# DigitalBackend_v1.net
KiCad netlist of a schematic drawn in EAGLE
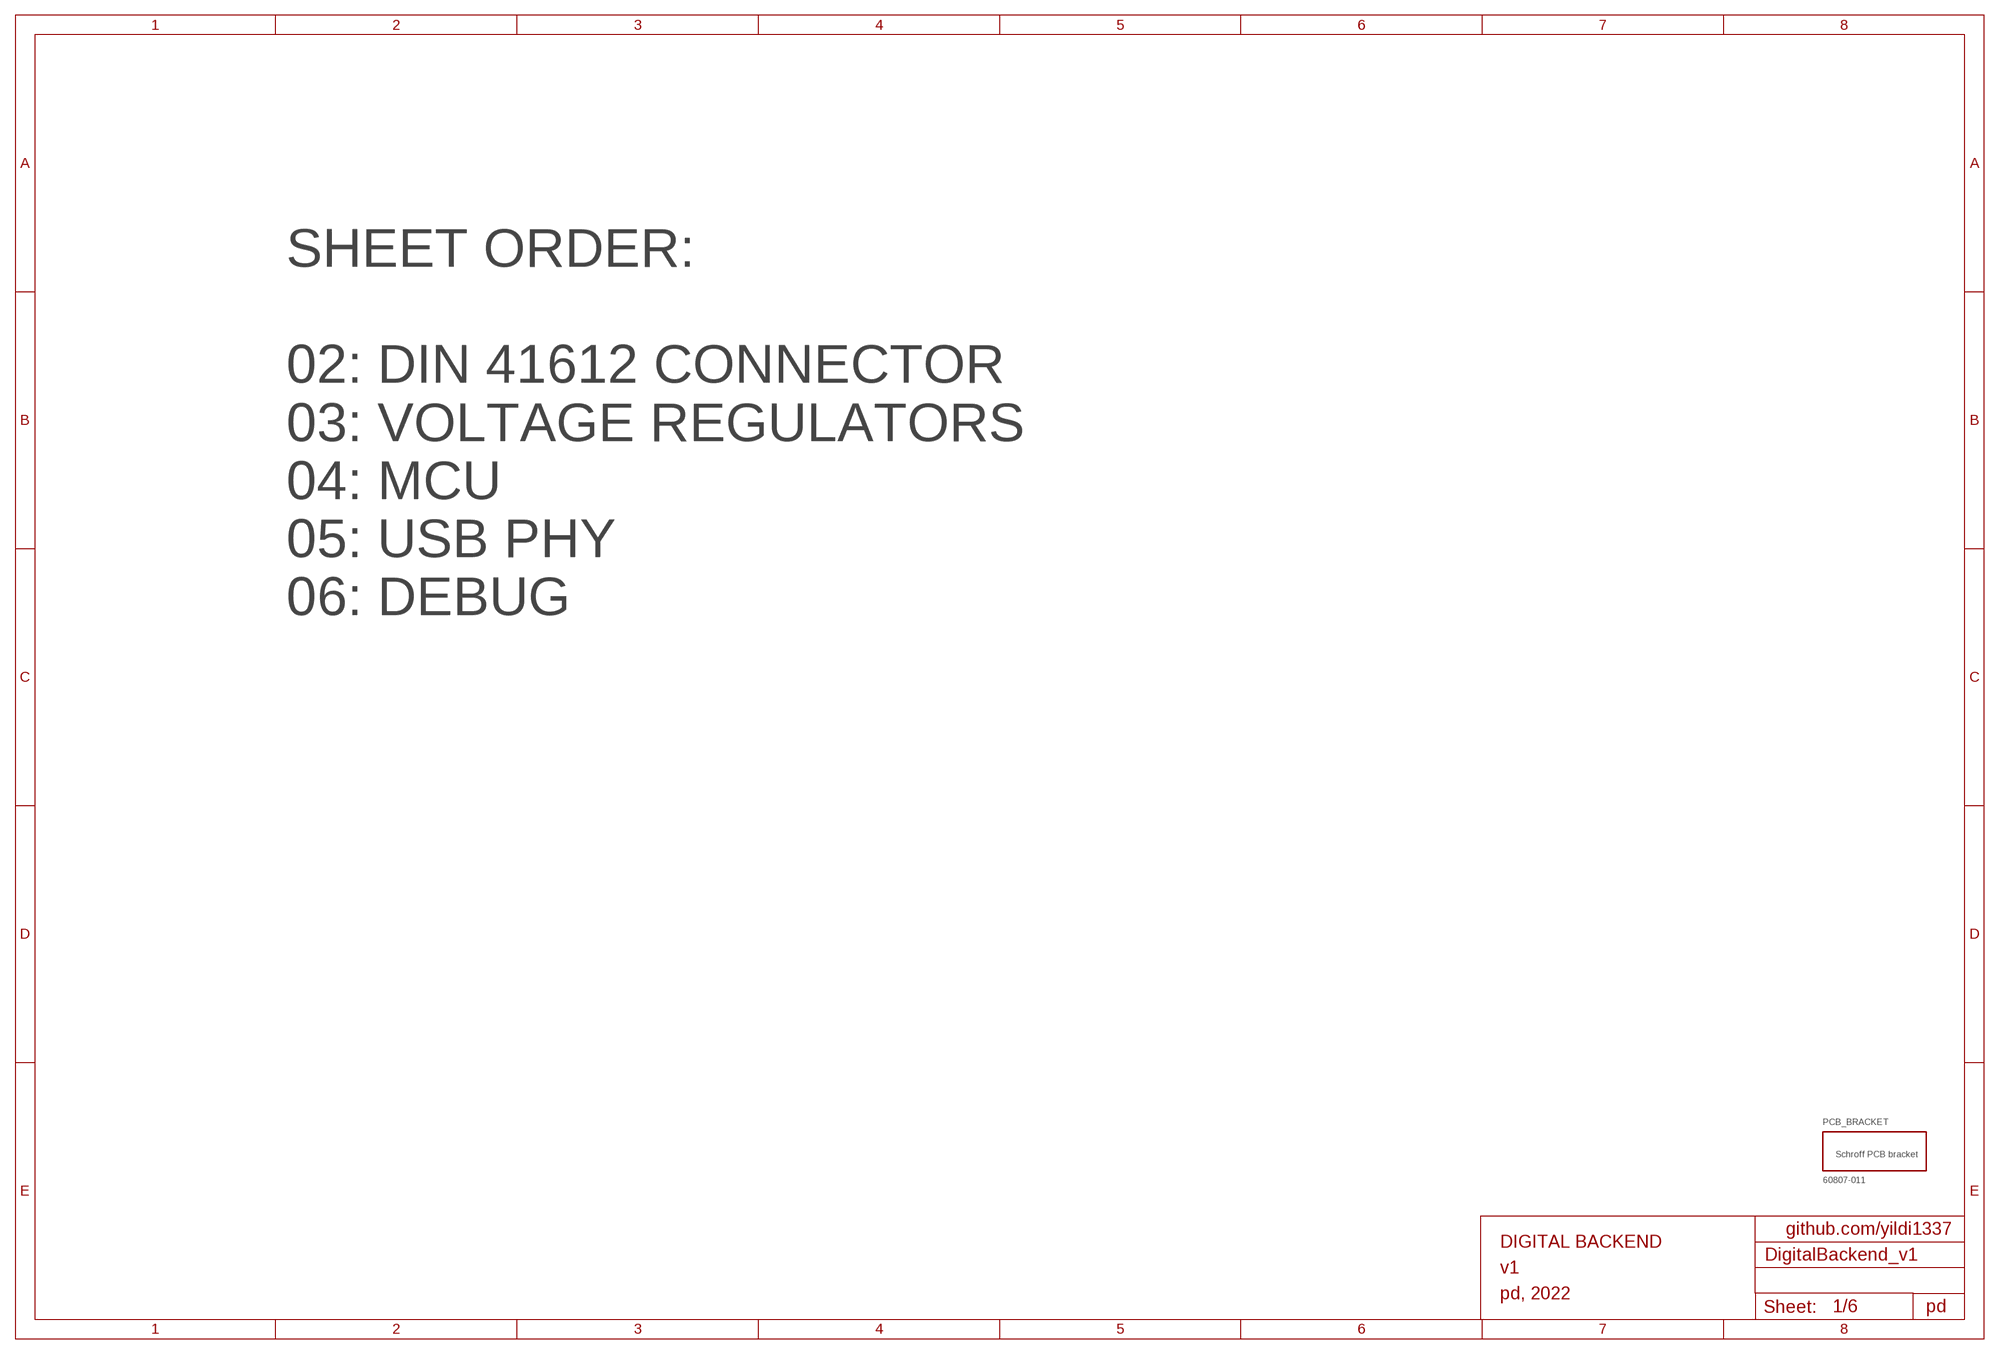
[diagram p0: schematic, sheet 1]
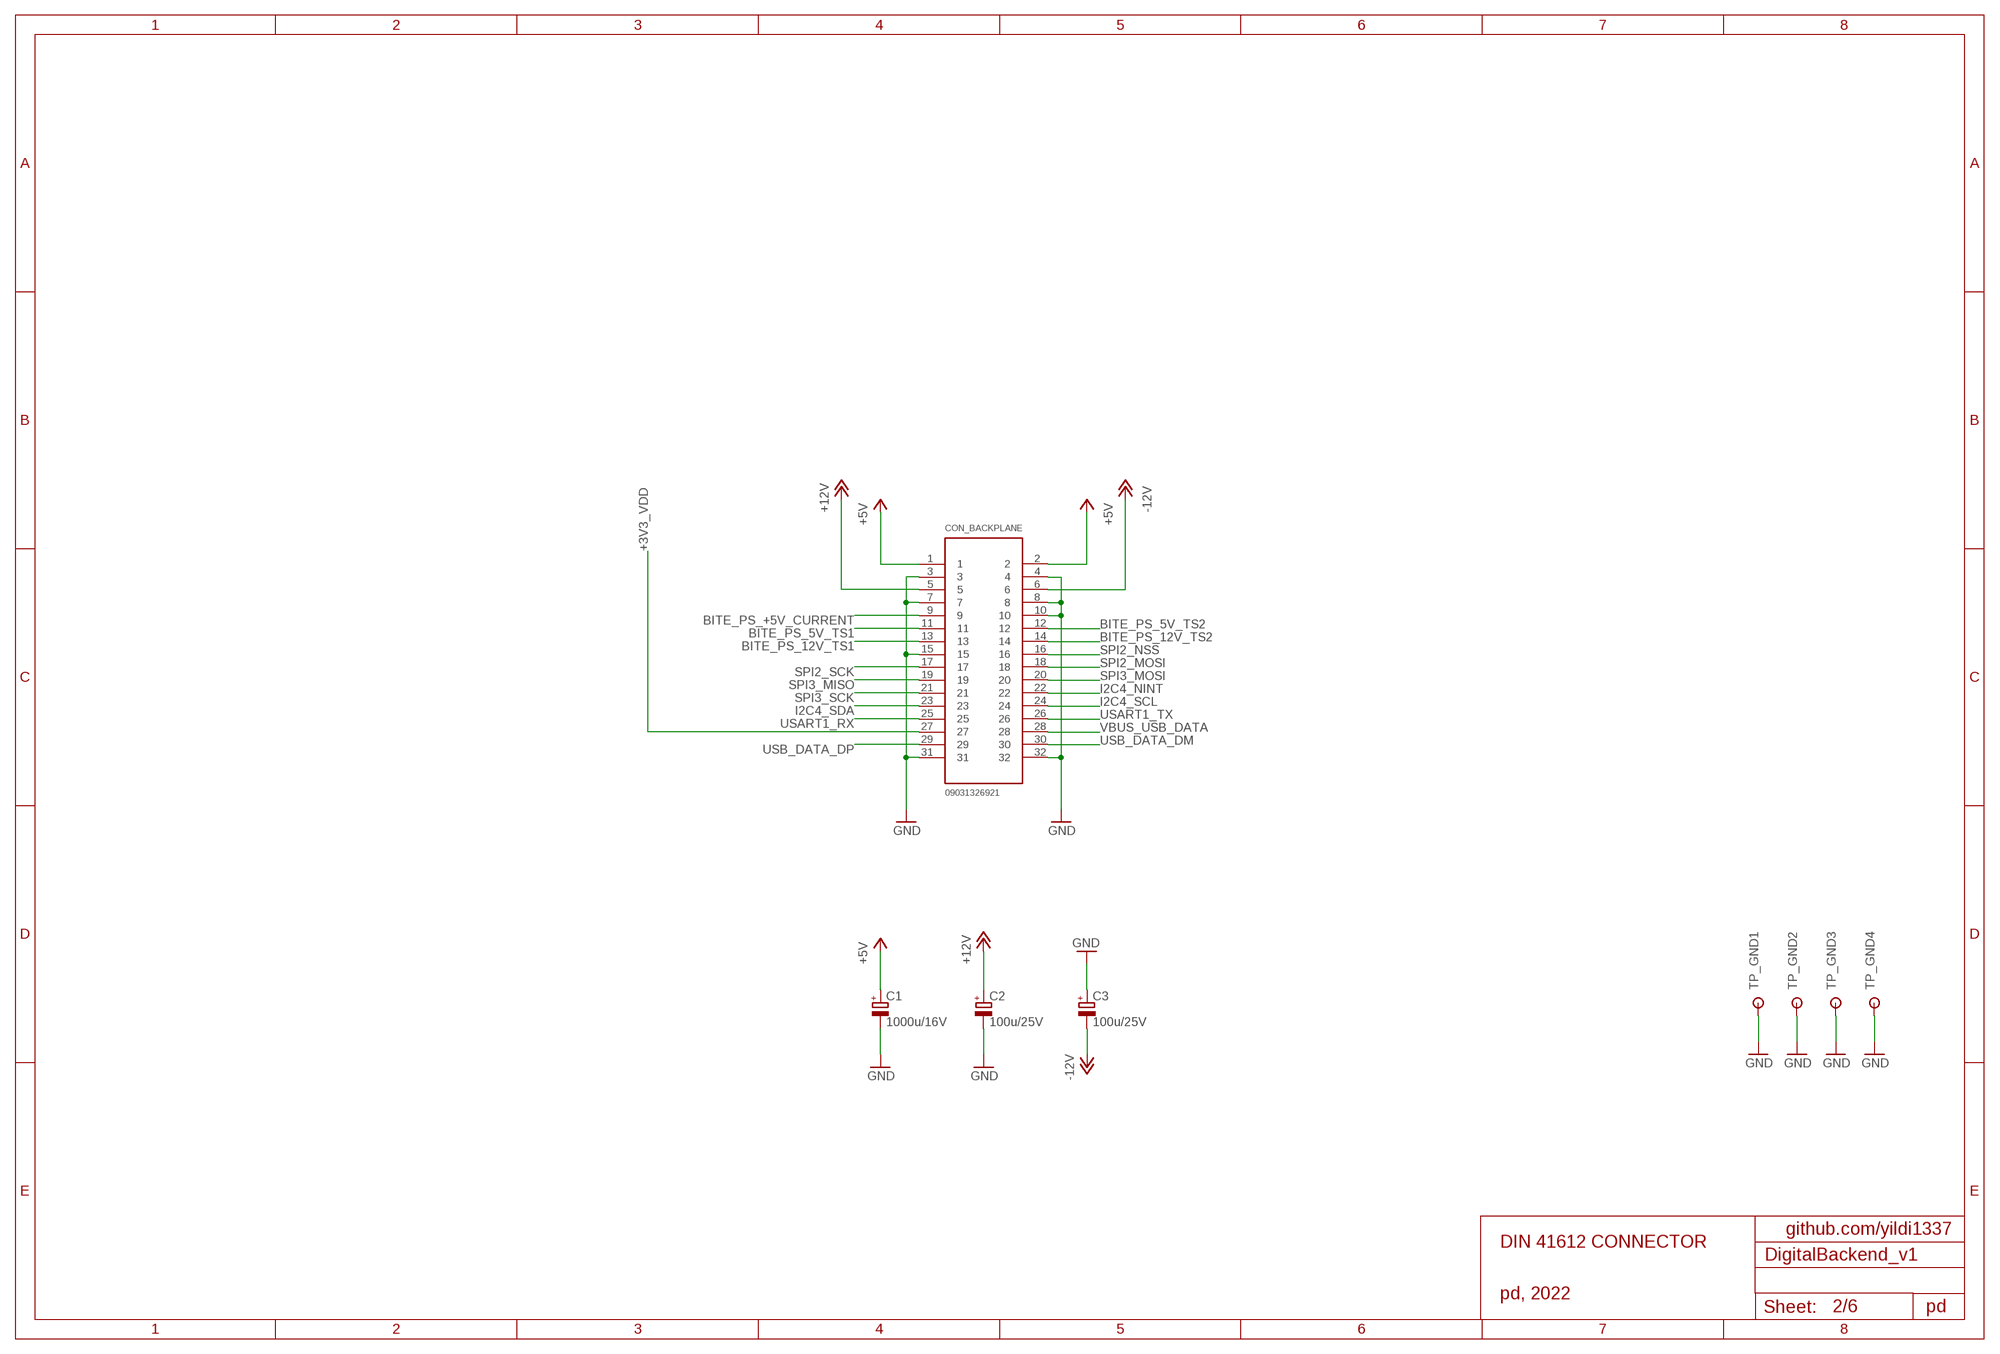
[diagram p1: schematic, sheet 2]
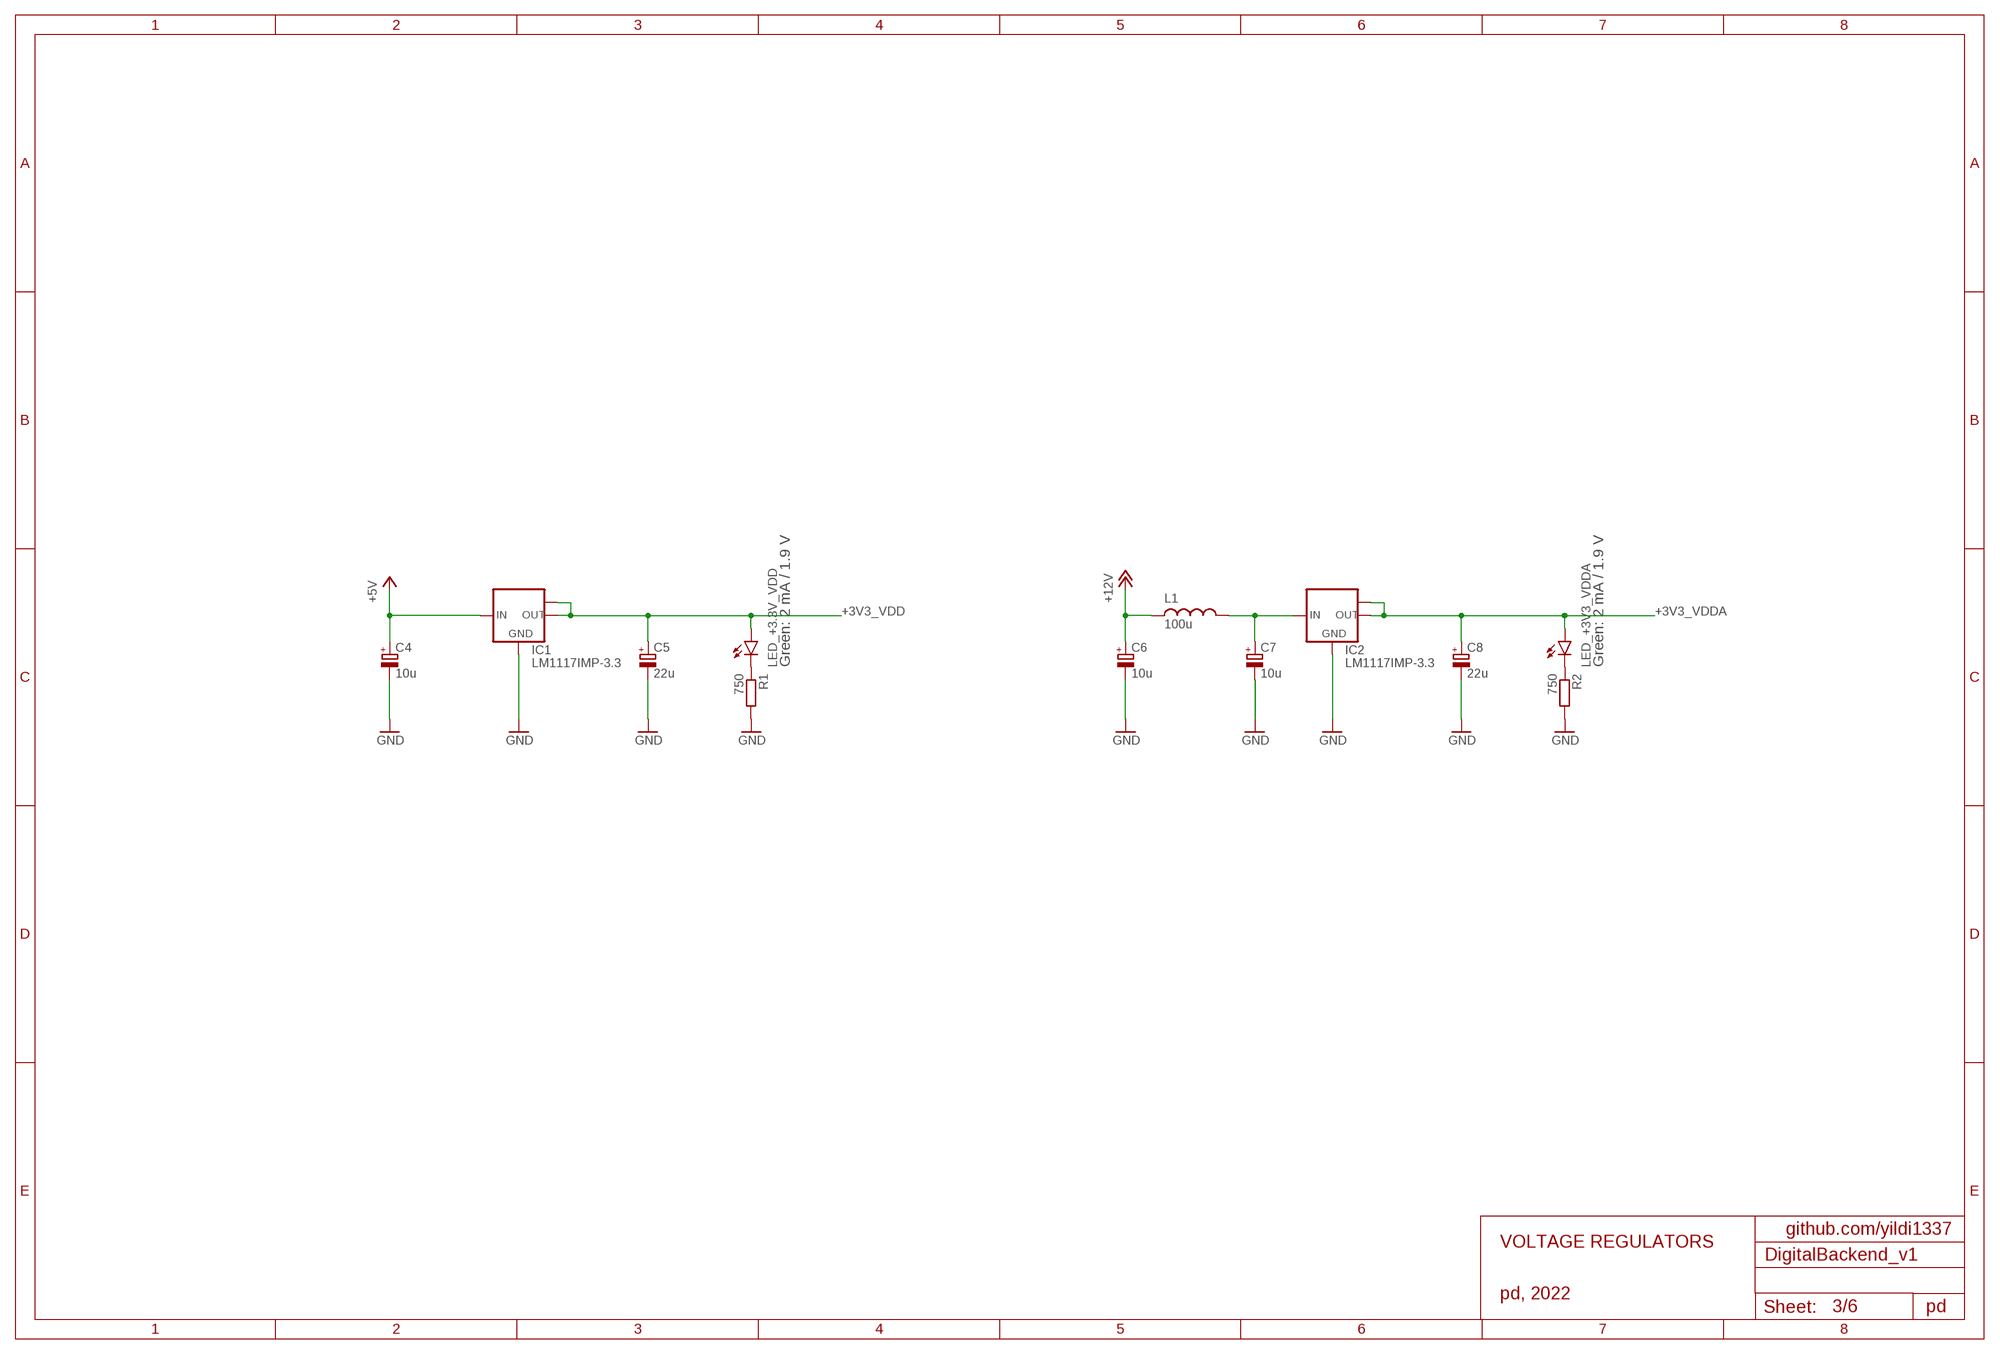
[diagram p2: schematic, sheet 3]
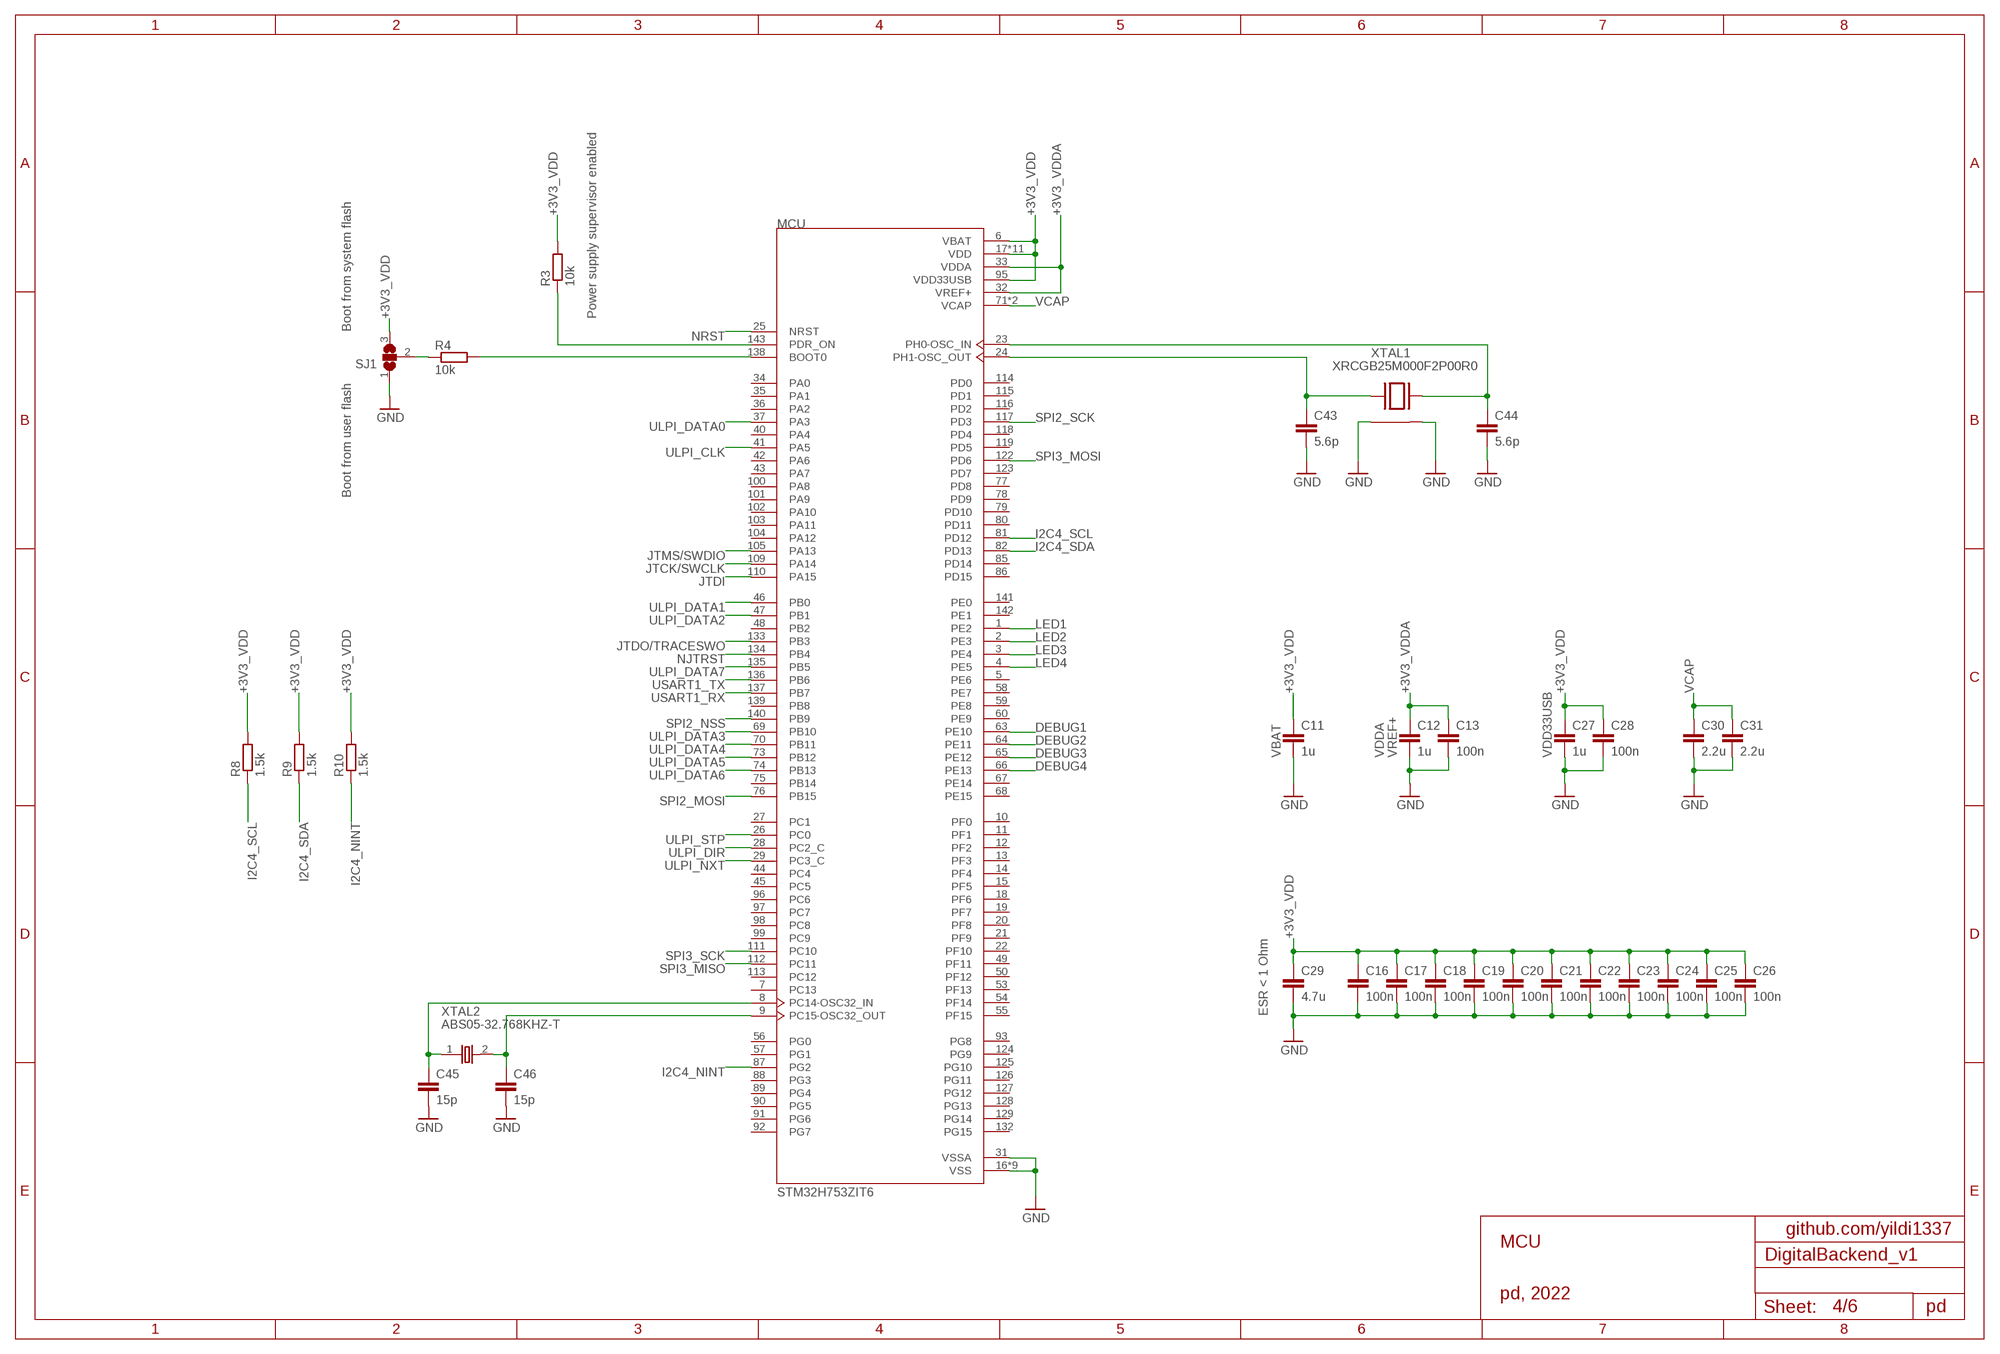
[diagram p3: schematic, sheet 4]
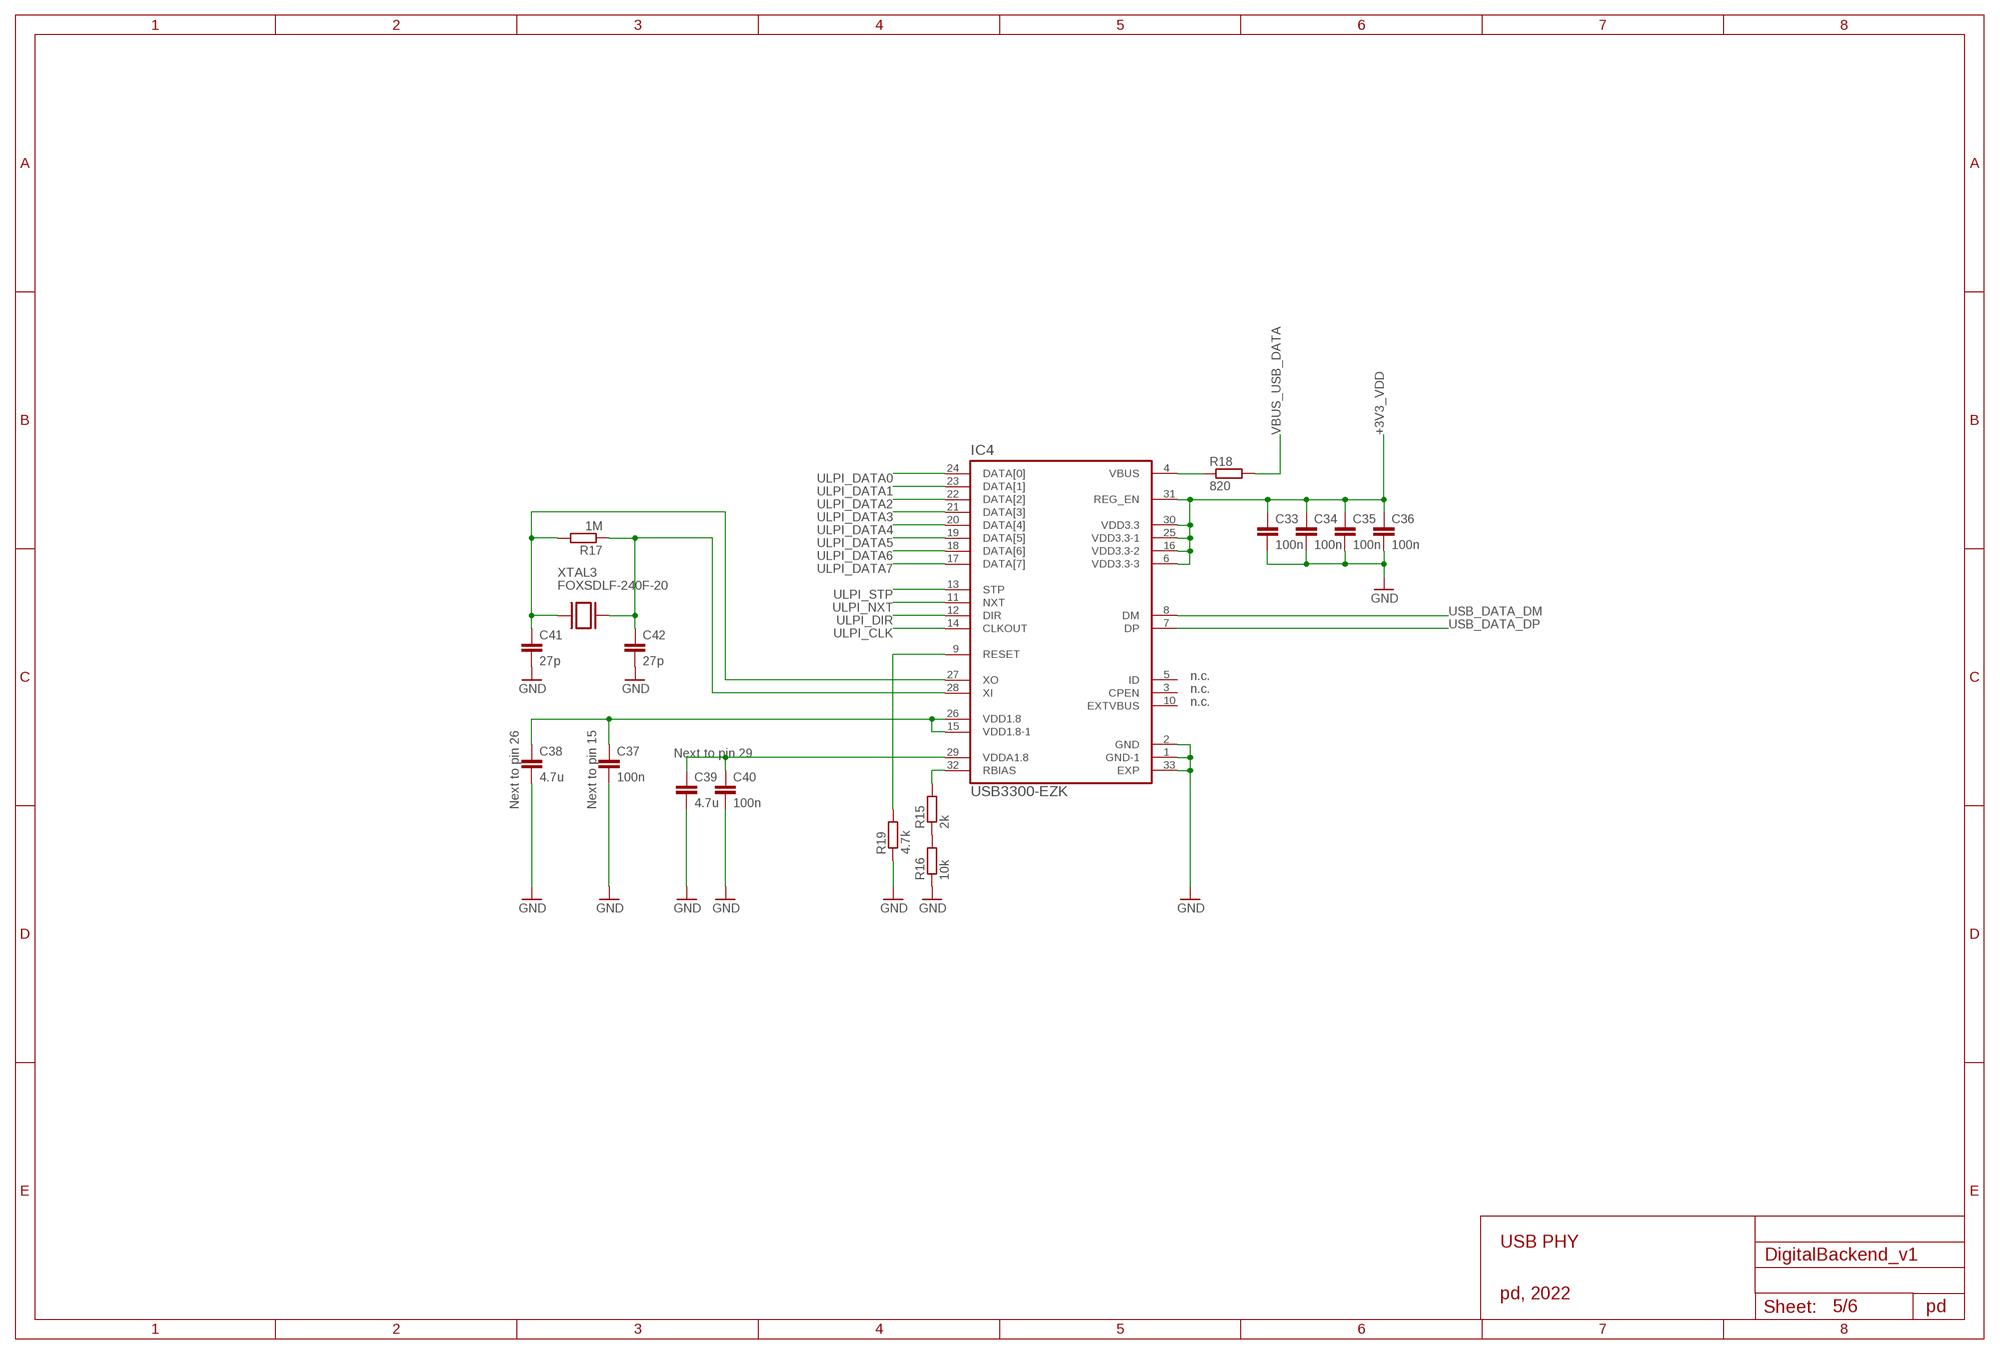
[diagram p4: schematic, sheet 5]
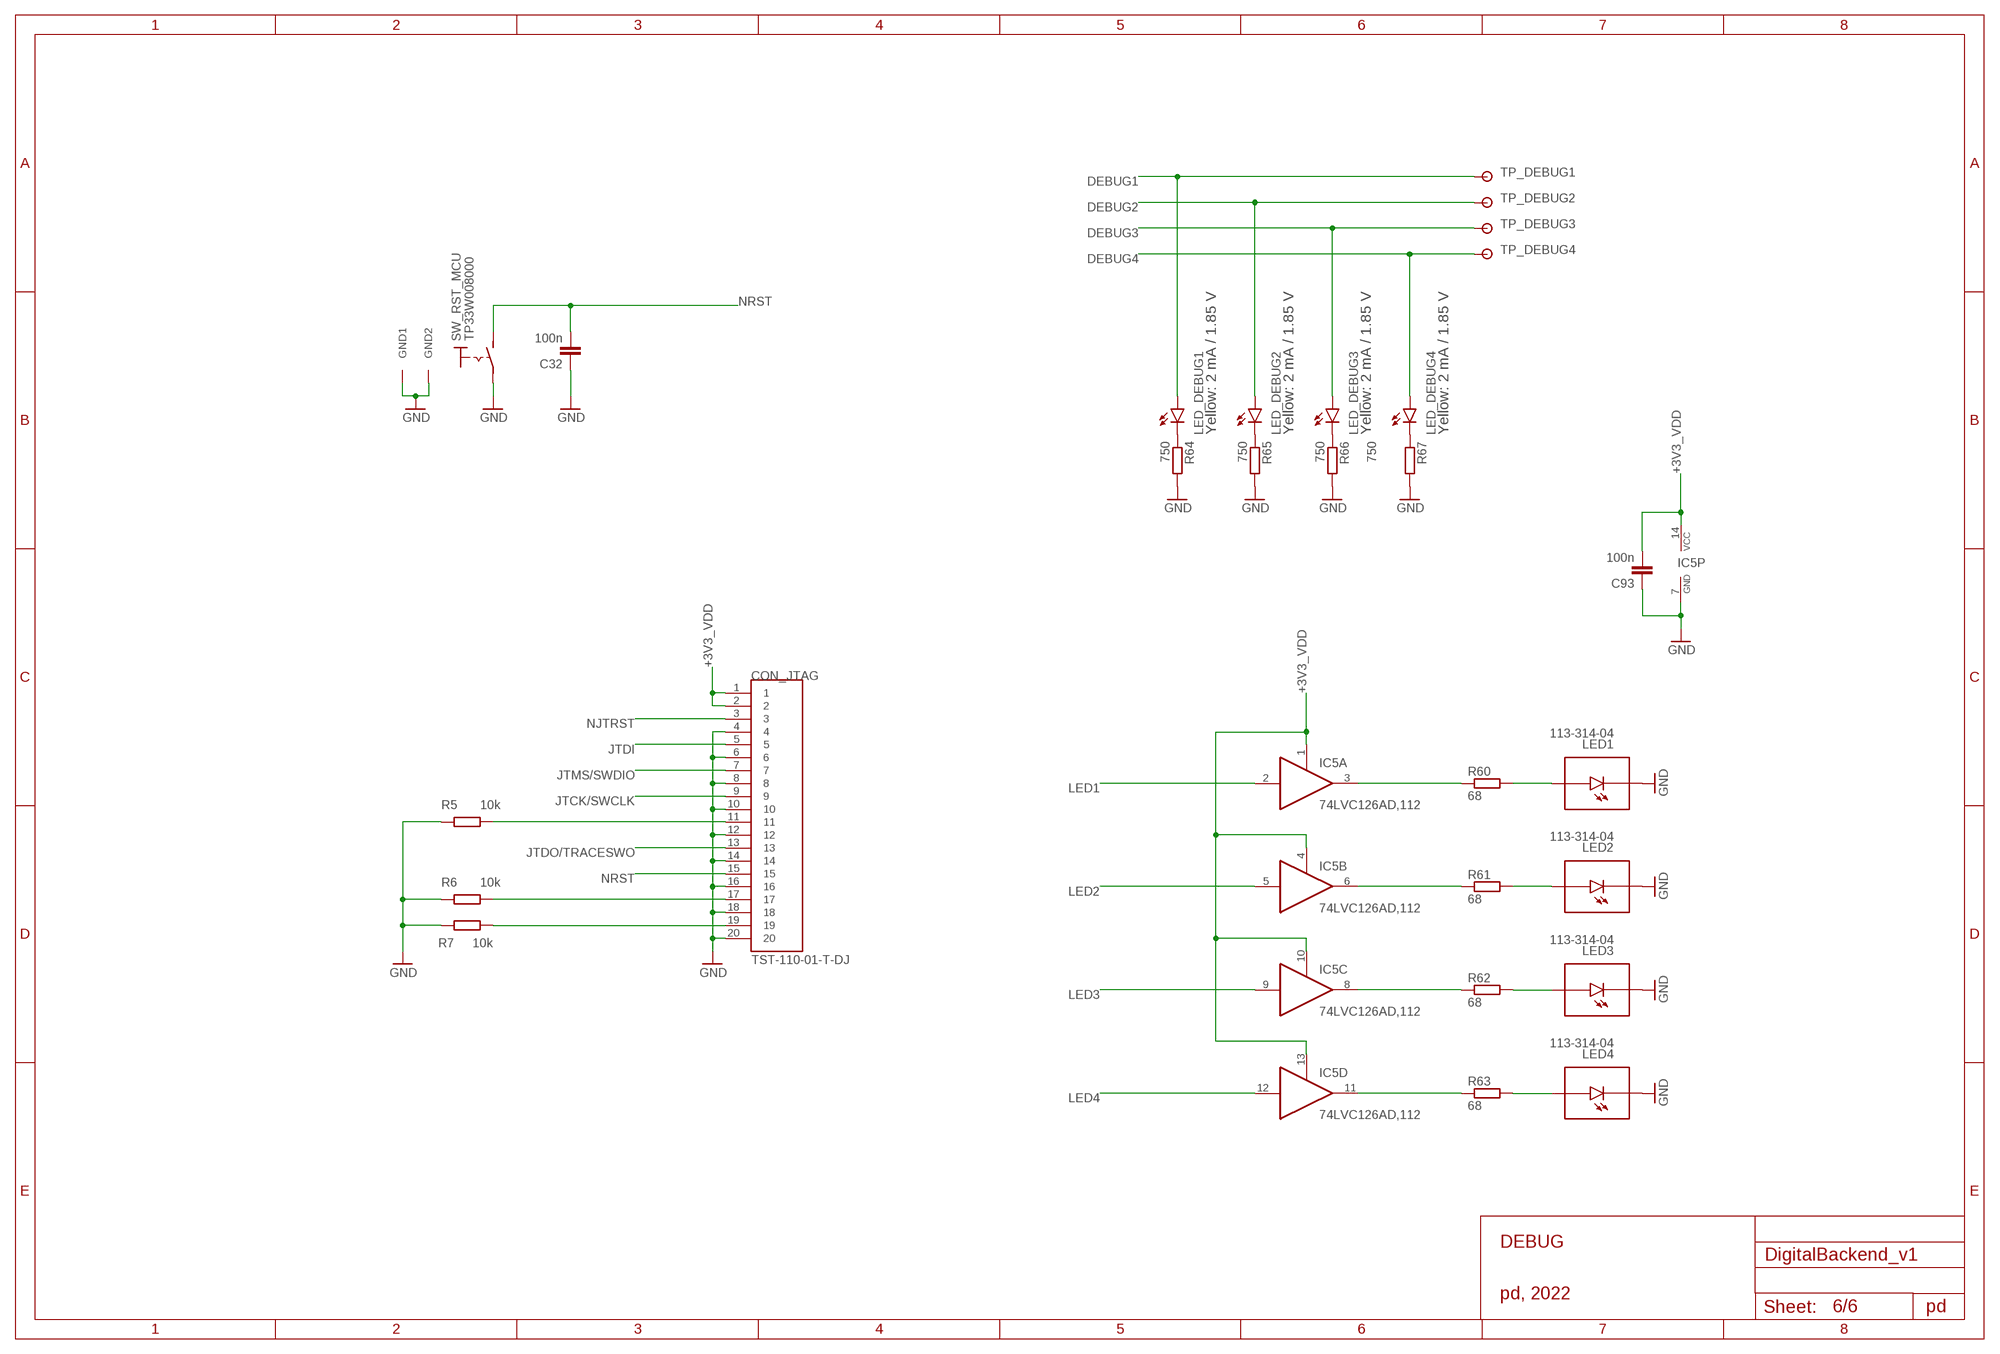
[diagram p5: schematic, sheet 6]

(export (version "E")
  (design (tool "Eeschema 10.0.6"))
  (components
    (comp (ref "C32")
      (value "100n")
      (footprint "eagle-import:C0603")
      (libsource (lib "eagle-import") (part "C-EUC0603"))
    )
    (comp (ref "C93")
      (value "100n")
      (footprint "eagle-import:C0603")
      (libsource (lib "eagle-import") (part "C-EUC0603"))
    )
    (comp (ref "CON_JTAG")
      (value "TST-110-01-T-DJ")
      (footprint "eagle-import:TST-110-01-T-D")
      (libsource (lib "eagle-import") (part "TST-110-01-T-DJ"))
    )
    (comp (ref "IC5")
      (value "74LVC126AD,112")
      (footprint "eagle-import:SO14")
      (libsource (lib "eagle-import") (part "74126DAC"))
    )
    (comp (ref "LED1")
      (value "113-314-04")
      (footprint "eagle-import:113-314-04")
      (libsource (lib "eagle-import") (part "113-314-04"))
    )
    (comp (ref "LED2")
      (value "113-314-04")
      (footprint "eagle-import:113-314-04")
      (libsource (lib "eagle-import") (part "113-314-04"))
    )
    (comp (ref "LED3")
      (value "113-314-04")
      (footprint "eagle-import:113-314-04")
      (libsource (lib "eagle-import") (part "113-314-04"))
    )
    (comp (ref "LED4")
      (value "113-314-04")
      (footprint "eagle-import:113-314-04")
      (libsource (lib "eagle-import") (part "113-314-04"))
    )
    (comp (ref "LED_DEBUG1")
      (value "LEDCHIP-LED0603")
      (footprint "eagle-import:CHIP-LED0603")
      (libsource (lib "eagle-import") (part "LEDCHIP-LED0603"))
    )
    (comp (ref "LED_DEBUG2")
      (value "LEDCHIP-LED0603")
      (footprint "eagle-import:CHIP-LED0603")
      (libsource (lib "eagle-import") (part "LEDCHIP-LED0603"))
    )
    (comp (ref "LED_DEBUG3")
      (value "LEDCHIP-LED0603")
      (footprint "eagle-import:CHIP-LED0603")
      (libsource (lib "eagle-import") (part "LEDCHIP-LED0603"))
    )
    (comp (ref "LED_DEBUG4")
      (value "LEDCHIP-LED0603")
      (footprint "eagle-import:CHIP-LED0603")
      (libsource (lib "eagle-import") (part "LEDCHIP-LED0603"))
    )
    (comp (ref "R5")
      (value "10k")
      (footprint "eagle-import:R0603")
      (libsource (lib "eagle-import") (part "R-EU_R0603"))
    )
    (comp (ref "R6")
      (value "10k")
      (footprint "eagle-import:R0603")
      (libsource (lib "eagle-import") (part "R-EU_R0603"))
    )
    (comp (ref "R7")
      (value "10k")
      (footprint "eagle-import:R0603")
      (libsource (lib "eagle-import") (part "R-EU_R0603"))
    )
    (comp (ref "R60")
      (value "68")
      (footprint "eagle-import:R0603")
      (libsource (lib "eagle-import") (part "R-EU_R0603"))
    )
    (comp (ref "R61")
      (value "68")
      (footprint "eagle-import:R0603")
      (libsource (lib "eagle-import") (part "R-EU_R0603"))
    )
    (comp (ref "R62")
      (value "68")
      (footprint "eagle-import:R0603")
      (libsource (lib "eagle-import") (part "R-EU_R0603"))
    )
    (comp (ref "R63")
      (value "68")
      (footprint "eagle-import:R0603")
      (libsource (lib "eagle-import") (part "R-EU_R0603"))
    )
    (comp (ref "R64")
      (value "750")
      (footprint "eagle-import:R0603")
      (libsource (lib "eagle-import") (part "R-EU_R0603"))
    )
    (comp (ref "R65")
      (value "750")
      (footprint "eagle-import:R0603")
      (libsource (lib "eagle-import") (part "R-EU_R0603"))
    )
    (comp (ref "R66")
      (value "750")
      (footprint "eagle-import:R0603")
      (libsource (lib "eagle-import") (part "R-EU_R0603"))
    )
    (comp (ref "R67")
      (value "750")
      (footprint "eagle-import:R0603")
      (libsource (lib "eagle-import") (part "R-EU_R0603"))
    )
    (comp (ref "SW_RST_MCU")
      (value "TP33W008000")
      (footprint "eagle-import:TP33W008000")
      (libsource (lib "eagle-import") (part "TP33W008000"))
    )
    (comp (ref "TP_DEBUG1")
      (value "RSPRO-1MM-TERMINAL-POST-2622034")
      (footprint "eagle-import:RSPRO-1MM-TERMINAL-POST-2622034")
      (libsource (lib "eagle-import") (part "RSPRO-1MM-TERMINAL-POST-2622034"))
    )
    (comp (ref "TP_DEBUG2")
      (value "RSPRO-1MM-TERMINAL-POST-2622034")
      (footprint "eagle-import:RSPRO-1MM-TERMINAL-POST-2622034")
      (libsource (lib "eagle-import") (part "RSPRO-1MM-TERMINAL-POST-2622034"))
    )
    (comp (ref "TP_DEBUG3")
      (value "RSPRO-1MM-TERMINAL-POST-2622034")
      (footprint "eagle-import:RSPRO-1MM-TERMINAL-POST-2622034")
      (libsource (lib "eagle-import") (part "RSPRO-1MM-TERMINAL-POST-2622034"))
    )
    (comp (ref "TP_DEBUG4")
      (value "RSPRO-1MM-TERMINAL-POST-2622034")
      (footprint "eagle-import:RSPRO-1MM-TERMINAL-POST-2622034")
      (libsource (lib "eagle-import") (part "RSPRO-1MM-TERMINAL-POST-2622034"))
    )
    (comp (ref "C1")
      (value "1000u/16V")
      (footprint "eagle-import:153CLV-1010")
      (libsource (lib "eagle-import") (part "rcl_18640681_CPOL-EU153CLV-1010"))
    )
    (comp (ref "C2")
      (value "100u/25V")
      (footprint "eagle-import:153CLV-0810")
      (libsource (lib "eagle-import") (part "rcl_18640681_CPOL-EU153CLV-0810"))
    )
    (comp (ref "C3")
      (value "100u/25V")
      (footprint "eagle-import:153CLV-0810")
      (libsource (lib "eagle-import") (part "rcl_18640681_CPOL-EU153CLV-0810"))
    )
    (comp (ref "CON_BACKPLANE")
      (value "09031326921")
      (footprint "eagle-import:09031326921")
      (libsource (lib "eagle-import") (part "09031326921"))
    )
    (comp (ref "TP_GND1")
      (value "RSPRO-1MM-TERMINAL-POST-2622034")
      (footprint "eagle-import:RSPRO-1MM-TERMINAL-POST-2622034")
      (libsource (lib "eagle-import") (part "RSPRO-1MM-TERMINAL-POST-2622034"))
    )
    (comp (ref "TP_GND2")
      (value "RSPRO-1MM-TERMINAL-POST-2622034")
      (footprint "eagle-import:RSPRO-1MM-TERMINAL-POST-2622034")
      (libsource (lib "eagle-import") (part "RSPRO-1MM-TERMINAL-POST-2622034"))
    )
    (comp (ref "TP_GND3")
      (value "RSPRO-1MM-TERMINAL-POST-2622034")
      (footprint "eagle-import:RSPRO-1MM-TERMINAL-POST-2622034")
      (libsource (lib "eagle-import") (part "RSPRO-1MM-TERMINAL-POST-2622034"))
    )
    (comp (ref "TP_GND4")
      (value "RSPRO-1MM-TERMINAL-POST-2622034")
      (footprint "eagle-import:RSPRO-1MM-TERMINAL-POST-2622034")
      (libsource (lib "eagle-import") (part "RSPRO-1MM-TERMINAL-POST-2622034"))
    )
    (comp (ref "C4")
      (value "10u")
      (footprint "eagle-import:CT3216")
      (libsource (lib "eagle-import") (part "CPOL-EUCT3216"))
    )
    (comp (ref "C5")
      (value "22u")
      (footprint "eagle-import:CT6032")
      (libsource (lib "eagle-import") (part "CPOL-EUCT6032"))
    )
    (comp (ref "C6")
      (value "10u")
      (footprint "eagle-import:CT3216")
      (libsource (lib "eagle-import") (part "CPOL-EUCT3216"))
    )
    (comp (ref "C7")
      (value "10u")
      (footprint "eagle-import:CT3216")
      (libsource (lib "eagle-import") (part "CPOL-EUCT3216"))
    )
    (comp (ref "C8")
      (value "22u")
      (footprint "eagle-import:CT6032")
      (libsource (lib "eagle-import") (part "CPOL-EUCT6032"))
    )
    (comp (ref "IC1")
      (value "LM1117IMP-3.3")
      (footprint "eagle-import:SOT223")
      (libsource (lib "eagle-import") (part "LM1117_23469477_LM1117IMPX-3.3"))
    )
    (comp (ref "IC2")
      (value "LM1117IMP-3.3")
      (footprint "eagle-import:SOT223")
      (libsource (lib "eagle-import") (part "LM1117IMPX-3.3"))
    )
    (comp (ref "L1")
      (value "100u")
      (footprint "eagle-import:VLS6045AF-101M")
      (libsource (lib "eagle-import") (part "VLS6045AF-101M"))
    )
    (comp (ref "LED_+3.3V_VDD")
      (value "LEDCHIP-LED0603")
      (footprint "eagle-import:CHIP-LED0603")
      (libsource (lib "eagle-import") (part "LEDCHIP-LED0603"))
    )
    (comp (ref "LED_+3V3_VDDA")
      (value "LEDCHIP-LED0603")
      (footprint "eagle-import:CHIP-LED0603")
      (libsource (lib "eagle-import") (part "LEDCHIP-LED0603"))
    )
    (comp (ref "R1")
      (value "750")
      (footprint "eagle-import:R0603")
      (libsource (lib "eagle-import") (part "R-EU_R0603"))
    )
    (comp (ref "R2")
      (value "750")
      (footprint "eagle-import:R0603")
      (libsource (lib "eagle-import") (part "R-EU_R0603"))
    )
    (comp (ref "C33")
      (value "100n")
      (footprint "eagle-import:C0603")
      (libsource (lib "eagle-import") (part "C-EUC0603"))
    )
    (comp (ref "C34")
      (value "100n")
      (footprint "eagle-import:C0603")
      (libsource (lib "eagle-import") (part "C-EUC0603"))
    )
    (comp (ref "C35")
      (value "100n")
      (footprint "eagle-import:C0603")
      (libsource (lib "eagle-import") (part "C-EUC0603"))
    )
    (comp (ref "C36")
      (value "100n")
      (footprint "eagle-import:C0603")
      (libsource (lib "eagle-import") (part "C-EUC0603"))
    )
    (comp (ref "C37")
      (value "100n")
      (footprint "eagle-import:C0603")
      (libsource (lib "eagle-import") (part "C-EUC0603"))
    )
    (comp (ref "C38")
      (value "4.7u")
      (footprint "eagle-import:C0603")
      (libsource (lib "eagle-import") (part "C-EUC0603"))
    )
    (comp (ref "C39")
      (value "4.7u")
      (footprint "eagle-import:C0603")
      (libsource (lib "eagle-import") (part "C-EUC0603"))
    )
    (comp (ref "C40")
      (value "100n")
      (footprint "eagle-import:C0603")
      (libsource (lib "eagle-import") (part "C-EUC0603"))
    )
    (comp (ref "C41")
      (value "27p")
      (footprint "eagle-import:C0603")
      (libsource (lib "eagle-import") (part "C-EUC0603"))
    )
    (comp (ref "C42")
      (value "27p")
      (footprint "eagle-import:C0603")
      (libsource (lib "eagle-import") (part "C-EUC0603"))
    )
    (comp (ref "IC4")
      (value "USB3300-EZK")
      (footprint "eagle-import:USB3300-EZK")
      (libsource (lib "eagle-import") (part "USB3300-EZK"))
    )
    (comp (ref "R15")
      (value "2k")
      (footprint "eagle-import:R0603")
      (libsource (lib "eagle-import") (part "R-EU_R0603"))
    )
    (comp (ref "R16")
      (value "10k")
      (footprint "eagle-import:R0603")
      (libsource (lib "eagle-import") (part "R-EU_R0603"))
    )
    (comp (ref "R17")
      (value "1M")
      (footprint "eagle-import:R0603")
      (libsource (lib "eagle-import") (part "R-EU_R0603"))
    )
    (comp (ref "R18")
      (value "820")
      (footprint "eagle-import:R0603")
      (libsource (lib "eagle-import") (part "R-EU_R0603"))
    )
    (comp (ref "R19")
      (value "4.7k")
      (footprint "eagle-import:R0603")
      (libsource (lib "eagle-import") (part "R-EU_R0603"))
    )
    (comp (ref "XTAL3")
      (value "FOXSDLF-240F-20")
      (footprint "eagle-import:FOXSDLF-240F-20")
      (libsource (lib "eagle-import") (part "FOXSDLF-240F-20"))
    )
    (comp (ref "PCB_BRACKET")
      (value "60807-011")
      (footprint "eagle-import:60807-011")
      (libsource (lib "eagle-import") (part "60807-011"))
    )
    (comp (ref "C11")
      (value "1u")
      (footprint "eagle-import:C0603")
      (libsource (lib "eagle-import") (part "C-EUC0603"))
    )
    (comp (ref "C12")
      (value "1u")
      (footprint "eagle-import:C0603")
      (libsource (lib "eagle-import") (part "C-EUC0603"))
    )
    (comp (ref "C13")
      (value "100n")
      (footprint "eagle-import:C0603")
      (libsource (lib "eagle-import") (part "C-EUC0603"))
    )
    (comp (ref "C16")
      (value "100n")
      (footprint "eagle-import:C0603")
      (libsource (lib "eagle-import") (part "C-EUC0603"))
    )
    (comp (ref "C17")
      (value "100n")
      (footprint "eagle-import:C0603")
      (libsource (lib "eagle-import") (part "C-EUC0603"))
    )
    (comp (ref "C18")
      (value "100n")
      (footprint "eagle-import:C0603")
      (libsource (lib "eagle-import") (part "C-EUC0603"))
    )
    (comp (ref "C19")
      (value "100n")
      (footprint "eagle-import:C0603")
      (libsource (lib "eagle-import") (part "C-EUC0603"))
    )
    (comp (ref "C20")
      (value "100n")
      (footprint "eagle-import:C0603")
      (libsource (lib "eagle-import") (part "C-EUC0603"))
    )
    (comp (ref "C21")
      (value "100n")
      (footprint "eagle-import:C0603")
      (libsource (lib "eagle-import") (part "C-EUC0603"))
    )
    (comp (ref "C22")
      (value "100n")
      (footprint "eagle-import:C0603")
      (libsource (lib "eagle-import") (part "C-EUC0603"))
    )
    (comp (ref "C23")
      (value "100n")
      (footprint "eagle-import:C0603")
      (libsource (lib "eagle-import") (part "C-EUC0603"))
    )
    (comp (ref "C24")
      (value "100n")
      (footprint "eagle-import:C0603")
      (libsource (lib "eagle-import") (part "C-EUC0603"))
    )
    (comp (ref "C25")
      (value "100n")
      (footprint "eagle-import:C0603")
      (libsource (lib "eagle-import") (part "C-EUC0603"))
    )
    (comp (ref "C26")
      (value "100n")
      (footprint "eagle-import:C0603")
      (libsource (lib "eagle-import") (part "C-EUC0603"))
    )
    (comp (ref "C27")
      (value "1u")
      (footprint "eagle-import:C0603")
      (libsource (lib "eagle-import") (part "C-EUC0603"))
    )
    (comp (ref "C28")
      (value "100n")
      (footprint "eagle-import:C0603")
      (libsource (lib "eagle-import") (part "C-EUC0603"))
    )
    (comp (ref "C29")
      (value "4.7u")
      (footprint "eagle-import:C0603")
      (libsource (lib "eagle-import") (part "C-EUC0603"))
    )
    (comp (ref "C30")
      (value "2.2u")
      (footprint "eagle-import:C0603")
      (libsource (lib "eagle-import") (part "C-EUC0603"))
    )
    (comp (ref "C31")
      (value "2.2u")
      (footprint "eagle-import:C0603")
      (libsource (lib "eagle-import") (part "C-EUC0603"))
    )
    (comp (ref "C43")
      (value "5.6p")
      (footprint "eagle-import:C0603")
      (libsource (lib "eagle-import") (part "C-EUC0603"))
    )
    (comp (ref "C44")
      (value "5.6p")
      (footprint "eagle-import:C0603")
      (libsource (lib "eagle-import") (part "C-EUC0603"))
    )
    (comp (ref "C45")
      (value "15p")
      (footprint "eagle-import:C0603")
      (libsource (lib "eagle-import") (part "C-EUC0603"))
    )
    (comp (ref "C46")
      (value "15p")
      (footprint "eagle-import:C0603")
      (libsource (lib "eagle-import") (part "C-EUC0603"))
    )
    (comp (ref "MCU")
      (value "STM32H753ZIT6")
      (footprint "eagle-import:LQFP144")
      (libsource (lib "eagle-import") (part "STM32H753ZIT6"))
    )
    (comp (ref "R3")
      (value "10k")
      (footprint "eagle-import:R0603")
      (libsource (lib "eagle-import") (part "R-EU_R0603"))
    )
    (comp (ref "R4")
      (value "10k")
      (footprint "eagle-import:R0603")
      (libsource (lib "eagle-import") (part "R-EU_R0603"))
    )
    (comp (ref "R8")
      (value "1.5k")
      (footprint "eagle-import:R0603")
      (libsource (lib "eagle-import") (part "R-EU_R0603"))
    )
    (comp (ref "R9")
      (value "1.5k")
      (footprint "eagle-import:R0603")
      (libsource (lib "eagle-import") (part "R-EU_R0603"))
    )
    (comp (ref "R10")
      (value "1.5k")
      (footprint "eagle-import:R0603")
      (libsource (lib "eagle-import") (part "R-EU_R0603"))
    )
    (comp (ref "SJ1")
      (value "SJ2W")
      (footprint "eagle-import:SJ_2")
      (libsource (lib "eagle-import") (part "SJ2W"))
    )
    (comp (ref "XTAL1")
      (value "XRCGB25M000F2P00R0")
      (footprint "eagle-import:XRCGB25M000F2P00R0")
      (libsource (lib "eagle-import") (part "XRCGB25M000F2P00R0"))
    )
    (comp (ref "XTAL2")
      (value "ABS05-32.768KHZ-T")
      (footprint "eagle-import:ABS05-32.768KHZ-T")
      (libsource (lib "eagle-import") (part "ABS05-32.768KHZ-T"))
    )
  )
  (nets
    (net (code "1") (name "+3V3_VDD") (class "Default")
      (node (ref "C11") (pin "1") (pinfunction "1_1") (pintype "passive"))
      (node (ref "C16") (pin "1") (pinfunction "1_1") (pintype "passive"))
      (node (ref "C17") (pin "1") (pinfunction "1_1") (pintype "passive"))
      (node (ref "C18") (pin "1") (pinfunction "1_1") (pintype "passive"))
      (node (ref "C19") (pin "1") (pinfunction "1_1") (pintype "passive"))
      (node (ref "C20") (pin "1") (pinfunction "1_1") (pintype "passive"))
      (node (ref "C21") (pin "1") (pinfunction "1_1") (pintype "passive"))
      (node (ref "C22") (pin "1") (pinfunction "1_1") (pintype "passive"))
      (node (ref "C23") (pin "1") (pinfunction "1_1") (pintype "passive"))
      (node (ref "C24") (pin "1") (pinfunction "1_1") (pintype "passive"))
      (node (ref "C25") (pin "1") (pinfunction "1_1") (pintype "passive"))
      (node (ref "C26") (pin "1") (pinfunction "1_1") (pintype "passive"))
      (node (ref "C27") (pin "1") (pinfunction "1_1") (pintype "passive"))
      (node (ref "C28") (pin "1") (pinfunction "1_1") (pintype "passive"))
      (node (ref "C29") (pin "1") (pinfunction "1_1") (pintype "passive"))
      (node (ref "C33") (pin "1") (pinfunction "1_1") (pintype "passive"))
      (node (ref "C34") (pin "1") (pinfunction "1_1") (pintype "passive"))
      (node (ref "C35") (pin "1") (pinfunction "1_1") (pintype "passive"))
      (node (ref "C36") (pin "1") (pinfunction "1_1") (pintype "passive"))
      (node (ref "C5") (pin "+") (pinfunction "+_+") (pintype "passive"))
      (node (ref "C93") (pin "2") (pinfunction "2_2") (pintype "passive"))
      (node (ref "CON_BACKPLANE") (pin "27") (pinfunction "27_27") (pintype "bidirectional"))
      (node (ref "CON_JTAG") (pin "1") (pinfunction "1_1") (pintype "passive"))
      (node (ref "CON_JTAG") (pin "2") (pinfunction "2_2") (pintype "passive"))
      (node (ref "IC1") (pin "2") (pinfunction "OUT_2") (pintype "passive"))
      (node (ref "IC1") (pin "TAB") (pinfunction "OUT1_TAB") (pintype "passive"))
      (node (ref "IC4") (pin "16") (pinfunction "VDD3.3-2_16") (pintype "power_in"))
      (node (ref "IC4") (pin "25") (pinfunction "VDD3.3-1_25") (pintype "power_in"))
      (node (ref "IC4") (pin "30") (pinfunction "VDD3.3_30") (pintype "power_in"))
      (node (ref "IC4") (pin "31") (pinfunction "REG_EN_31") (pintype "bidirectional"))
      (node (ref "IC4") (pin "6") (pinfunction "VDD3.3-3_6") (pintype "power_in"))
      (node (ref "IC5") (pin "1") (pinfunction "OE_1") (pintype "input"))
      (node (ref "IC5") (pin "10") (pinfunction "OE_10") (pintype "input"))
      (node (ref "IC5") (pin "13") (pinfunction "OE_13") (pintype "input"))
      (node (ref "IC5") (pin "14") (pinfunction "VCC_14") (pintype "power_in"))
      (node (ref "IC5") (pin "4") (pinfunction "OE_4") (pintype "input"))
      (node (ref "LED_+3.3V_VDD") (pin "A") (pinfunction "A_A") (pintype "passive"))
      (node (ref "MCU") (pin "108") (pinfunction "VDD_108") (pintype "power_in"))
      (node (ref "MCU") (pin "121") (pinfunction "VDD_121") (pintype "power_in"))
      (node (ref "MCU") (pin "131") (pinfunction "VDD_131") (pintype "power_in"))
      (node (ref "MCU") (pin "144") (pinfunction "VDD_144") (pintype "power_in"))
      (node (ref "MCU") (pin "17") (pinfunction "VDD_17") (pintype "power_in"))
      (node (ref "MCU") (pin "30") (pinfunction "VDD_30") (pintype "power_in"))
      (node (ref "MCU") (pin "39") (pinfunction "VDD_39") (pintype "power_in"))
      (node (ref "MCU") (pin "52") (pinfunction "VDD_52") (pintype "power_in"))
      (node (ref "MCU") (pin "6") (pinfunction "VBAT_6") (pintype "power_in"))
      (node (ref "MCU") (pin "62") (pinfunction "VDD_62") (pintype "power_in"))
      (node (ref "MCU") (pin "72") (pinfunction "VDD_72") (pintype "power_in"))
      (node (ref "MCU") (pin "84") (pinfunction "VDD_84") (pintype "power_in"))
      (node (ref "MCU") (pin "95") (pinfunction "VDD33USB_95") (pintype "power_in"))
      (node (ref "R10") (pin "2") (pinfunction "2_2") (pintype "passive"))
      (node (ref "R3") (pin "2") (pinfunction "2_2") (pintype "passive"))
      (node (ref "R8") (pin "2") (pinfunction "2_2") (pintype "passive"))
      (node (ref "R9") (pin "2") (pinfunction "2_2") (pintype "passive"))
      (node (ref "SJ1") (pin "3") (pinfunction "3_3") (pintype "passive"))
    )
    (net (code "2") (name "+3V3_VDDA") (class "Default")
      (node (ref "C12") (pin "1") (pinfunction "1_1") (pintype "passive"))
      (node (ref "C13") (pin "1") (pinfunction "1_1") (pintype "passive"))
      (node (ref "C8") (pin "+") (pinfunction "+_+") (pintype "passive"))
      (node (ref "IC2") (pin "2") (pinfunction "OUT_2") (pintype "passive"))
      (node (ref "IC2") (pin "TAB") (pinfunction "OUT1_TAB") (pintype "passive"))
      (node (ref "LED_+3V3_VDDA") (pin "A") (pinfunction "A_A") (pintype "passive"))
      (node (ref "MCU") (pin "32") (pinfunction "VREF+_32") (pintype "power_in"))
      (node (ref "MCU") (pin "33") (pinfunction "VDDA_33") (pintype "power_in"))
    )
    (net (code "3") (name "+5V") (class "Default")
      (node (ref "C1") (pin "+") (pinfunction "+_+") (pintype "passive"))
      (node (ref "C4") (pin "+") (pinfunction "+_+") (pintype "passive"))
      (node (ref "CON_BACKPLANE") (pin "1") (pinfunction "1_1") (pintype "bidirectional"))
      (node (ref "CON_BACKPLANE") (pin "2") (pinfunction "2_2") (pintype "bidirectional"))
      (node (ref "IC1") (pin "3") (pinfunction "IN_3") (pintype "input"))
    )
    (net (code "4") (name "+12V") (class "Default")
      (node (ref "C2") (pin "+") (pinfunction "+_+") (pintype "passive"))
      (node (ref "C6") (pin "+") (pinfunction "+_+") (pintype "passive"))
      (node (ref "CON_BACKPLANE") (pin "5") (pinfunction "5_5") (pintype "bidirectional"))
      (node (ref "L1") (pin "1") (pinfunction "1_1") (pintype "passive"))
    )
    (net (code "5") (name "-12V") (class "Default")
      (node (ref "C3") (pin "-") (pinfunction "-_-") (pintype "passive"))
      (node (ref "CON_BACKPLANE") (pin "6") (pinfunction "6_6") (pintype "bidirectional"))
    )
    (net (code "6") (name "BITE_PS_+5V_CURRENT") (class "Default")
      (node (ref "CON_BACKPLANE") (pin "9") (pinfunction "9_9") (pintype "bidirectional"))
    )
    (net (code "7") (name "BITE_PS_5V_TS1") (class "Default")
      (node (ref "CON_BACKPLANE") (pin "11") (pinfunction "11_11") (pintype "bidirectional"))
    )
    (net (code "8") (name "BITE_PS_5V_TS2") (class "Default")
      (node (ref "CON_BACKPLANE") (pin "12") (pinfunction "12_12") (pintype "bidirectional"))
    )
    (net (code "9") (name "BITE_PS_12V_TS1") (class "Default")
      (node (ref "CON_BACKPLANE") (pin "13") (pinfunction "13_13") (pintype "bidirectional"))
    )
    (net (code "10") (name "BITE_PS_12V_TS2") (class "Default")
      (node (ref "CON_BACKPLANE") (pin "14") (pinfunction "14_14") (pintype "bidirectional"))
    )
    (net (code "11") (name "DEBUG1") (class "Default")
      (node (ref "LED_DEBUG1") (pin "A") (pinfunction "A_A") (pintype "passive"))
      (node (ref "MCU") (pin "63") (pinfunction "PE10_63") (pintype "bidirectional"))
      (node (ref "TP_DEBUG1") (pin "P$1") (pinfunction "P$1_P$1") (pintype "bidirectional"))
    )
    (net (code "12") (name "DEBUG2") (class "Default")
      (node (ref "LED_DEBUG2") (pin "A") (pinfunction "A_A") (pintype "passive"))
      (node (ref "MCU") (pin "64") (pinfunction "PE11_64") (pintype "bidirectional"))
      (node (ref "TP_DEBUG2") (pin "P$1") (pinfunction "P$1_P$1") (pintype "bidirectional"))
    )
    (net (code "13") (name "DEBUG3") (class "Default")
      (node (ref "LED_DEBUG3") (pin "A") (pinfunction "A_A") (pintype "passive"))
      (node (ref "MCU") (pin "65") (pinfunction "PE12_65") (pintype "bidirectional"))
      (node (ref "TP_DEBUG3") (pin "P$1") (pinfunction "P$1_P$1") (pintype "bidirectional"))
    )
    (net (code "14") (name "DEBUG4") (class "Default")
      (node (ref "LED_DEBUG4") (pin "A") (pinfunction "A_A") (pintype "passive"))
      (node (ref "MCU") (pin "66") (pinfunction "PE13_66") (pintype "bidirectional"))
      (node (ref "TP_DEBUG4") (pin "P$1") (pinfunction "P$1_P$1") (pintype "bidirectional"))
    )
    (net (code "15") (name "GND") (class "Default")
      (node (ref "C1") (pin "-") (pinfunction "-_-") (pintype "passive"))
      (node (ref "C11") (pin "2") (pinfunction "2_2") (pintype "passive"))
      (node (ref "C12") (pin "2") (pinfunction "2_2") (pintype "passive"))
      (node (ref "C13") (pin "2") (pinfunction "2_2") (pintype "passive"))
      (node (ref "C16") (pin "2") (pinfunction "2_2") (pintype "passive"))
      (node (ref "C17") (pin "2") (pinfunction "2_2") (pintype "passive"))
      (node (ref "C18") (pin "2") (pinfunction "2_2") (pintype "passive"))
      (node (ref "C19") (pin "2") (pinfunction "2_2") (pintype "passive"))
      (node (ref "C2") (pin "-") (pinfunction "-_-") (pintype "passive"))
      (node (ref "C20") (pin "2") (pinfunction "2_2") (pintype "passive"))
      (node (ref "C21") (pin "2") (pinfunction "2_2") (pintype "passive"))
      (node (ref "C22") (pin "2") (pinfunction "2_2") (pintype "passive"))
      (node (ref "C23") (pin "2") (pinfunction "2_2") (pintype "passive"))
      (node (ref "C24") (pin "2") (pinfunction "2_2") (pintype "passive"))
      (node (ref "C25") (pin "2") (pinfunction "2_2") (pintype "passive"))
      (node (ref "C26") (pin "2") (pinfunction "2_2") (pintype "passive"))
      (node (ref "C27") (pin "2") (pinfunction "2_2") (pintype "passive"))
      (node (ref "C28") (pin "2") (pinfunction "2_2") (pintype "passive"))
      (node (ref "C29") (pin "2") (pinfunction "2_2") (pintype "passive"))
      (node (ref "C3") (pin "+") (pinfunction "+_+") (pintype "passive"))
      (node (ref "C30") (pin "2") (pinfunction "2_2") (pintype "passive"))
      (node (ref "C31") (pin "2") (pinfunction "2_2") (pintype "passive"))
      (node (ref "C32") (pin "1") (pinfunction "1_1") (pintype "passive"))
      (node (ref "C33") (pin "2") (pinfunction "2_2") (pintype "passive"))
      (node (ref "C34") (pin "2") (pinfunction "2_2") (pintype "passive"))
      (node (ref "C35") (pin "2") (pinfunction "2_2") (pintype "passive"))
      (node (ref "C36") (pin "2") (pinfunction "2_2") (pintype "passive"))
      (node (ref "C37") (pin "2") (pinfunction "2_2") (pintype "passive"))
      (node (ref "C38") (pin "2") (pinfunction "2_2") (pintype "passive"))
      (node (ref "C39") (pin "2") (pinfunction "2_2") (pintype "passive"))
      (node (ref "C4") (pin "-") (pinfunction "-_-") (pintype "passive"))
      (node (ref "C40") (pin "2") (pinfunction "2_2") (pintype "passive"))
      (node (ref "C41") (pin "2") (pinfunction "2_2") (pintype "passive"))
      (node (ref "C42") (pin "2") (pinfunction "2_2") (pintype "passive"))
      (node (ref "C43") (pin "2") (pinfunction "2_2") (pintype "passive"))
      (node (ref "C44") (pin "2") (pinfunction "2_2") (pintype "passive"))
      (node (ref "C45") (pin "2") (pinfunction "2_2") (pintype "passive"))
      (node (ref "C46") (pin "2") (pinfunction "2_2") (pintype "passive"))
      (node (ref "C5") (pin "-") (pinfunction "-_-") (pintype "passive"))
      (node (ref "C6") (pin "-") (pinfunction "-_-") (pintype "passive"))
      (node (ref "C7") (pin "-") (pinfunction "-_-") (pintype "passive"))
      (node (ref "C8") (pin "-") (pinfunction "-_-") (pintype "passive"))
      (node (ref "C93") (pin "1") (pinfunction "1_1") (pintype "passive"))
      (node (ref "CON_BACKPLANE") (pin "10") (pinfunction "10_10") (pintype "bidirectional"))
      (node (ref "CON_BACKPLANE") (pin "15") (pinfunction "15_15") (pintype "bidirectional"))
      (node (ref "CON_BACKPLANE") (pin "3") (pinfunction "3_3") (pintype "bidirectional"))
      (node (ref "CON_BACKPLANE") (pin "31") (pinfunction "31_31") (pintype "bidirectional"))
      (node (ref "CON_BACKPLANE") (pin "32") (pinfunction "32_32") (pintype "bidirectional"))
      (node (ref "CON_BACKPLANE") (pin "4") (pinfunction "4_4") (pintype "bidirectional"))
      (node (ref "CON_BACKPLANE") (pin "7") (pinfunction "7_7") (pintype "bidirectional"))
      (node (ref "CON_BACKPLANE") (pin "8") (pinfunction "8_8") (pintype "bidirectional"))
      (node (ref "CON_JTAG") (pin "10") (pinfunction "10_10") (pintype "passive"))
      (node (ref "CON_JTAG") (pin "12") (pinfunction "12_12") (pintype "passive"))
      (node (ref "CON_JTAG") (pin "14") (pinfunction "14_14") (pintype "passive"))
      (node (ref "CON_JTAG") (pin "16") (pinfunction "16_16") (pintype "passive"))
      (node (ref "CON_JTAG") (pin "18") (pinfunction "18_18") (pintype "passive"))
      (node (ref "CON_JTAG") (pin "20") (pinfunction "20_20") (pintype "passive"))
      (node (ref "CON_JTAG") (pin "4") (pinfunction "4_4") (pintype "passive"))
      (node (ref "CON_JTAG") (pin "6") (pinfunction "6_6") (pintype "passive"))
      (node (ref "CON_JTAG") (pin "8") (pinfunction "8_8") (pintype "passive"))
      (node (ref "IC1") (pin "1") (pinfunction "GND_1") (pintype "input"))
      (node (ref "IC2") (pin "1") (pinfunction "GND_1") (pintype "input"))
      (node (ref "IC4") (pin "1") (pinfunction "GND-1_1") (pintype "power_in"))
      (node (ref "IC4") (pin "2") (pinfunction "GND_2") (pintype "power_in"))
      (node (ref "IC4") (pin "33") (pinfunction "EXP_33") (pintype "power_in"))
      (node (ref "IC5") (pin "7") (pinfunction "GND_7") (pintype "power_in"))
      (node (ref "LED1") (pin "-") (pinfunction "C_-") (pintype "passive"))
      (node (ref "LED2") (pin "-") (pinfunction "C_-") (pintype "passive"))
      (node (ref "LED3") (pin "-") (pinfunction "C_-") (pintype "passive"))
      (node (ref "LED4") (pin "-") (pinfunction "C_-") (pintype "passive"))
      (node (ref "MCU") (pin "107") (pinfunction "VSS_107") (pintype "power_in"))
      (node (ref "MCU") (pin "120") (pinfunction "VSS_120") (pintype "power_in"))
      (node (ref "MCU") (pin "130") (pinfunction "VSS_130") (pintype "power_in"))
      (node (ref "MCU") (pin "16") (pinfunction "VSS_16") (pintype "power_in"))
      (node (ref "MCU") (pin "31") (pinfunction "VSSA_31") (pintype "power_in"))
      (node (ref "MCU") (pin "38") (pinfunction "VSS_38") (pintype "power_in"))
      (node (ref "MCU") (pin "51") (pinfunction "VSS_51") (pintype "power_in"))
      (node (ref "MCU") (pin "61") (pinfunction "VSS_61") (pintype "power_in"))
      (node (ref "MCU") (pin "83") (pinfunction "VSS_83") (pintype "power_in"))
      (node (ref "MCU") (pin "94") (pinfunction "VSS_94") (pintype "power_in"))
      (node (ref "R1") (pin "2") (pinfunction "2_2") (pintype "passive"))
      (node (ref "R16") (pin "1") (pinfunction "1_1") (pintype "passive"))
      (node (ref "R19") (pin "1") (pinfunction "1_1") (pintype "passive"))
      (node (ref "R2") (pin "2") (pinfunction "2_2") (pintype "passive"))
      (node (ref "R5") (pin "1") (pinfunction "1_1") (pintype "passive"))
      (node (ref "R6") (pin "1") (pinfunction "1_1") (pintype "passive"))
      (node (ref "R64") (pin "2") (pinfunction "2_2") (pintype "passive"))
      (node (ref "R65") (pin "2") (pinfunction "2_2") (pintype "passive"))
      (node (ref "R66") (pin "2") (pinfunction "2_2") (pintype "passive"))
      (node (ref "R67") (pin "2") (pinfunction "2_2") (pintype "passive"))
      (node (ref "R7") (pin "1") (pinfunction "1_1") (pintype "passive"))
      (node (ref "SJ1") (pin "1") (pinfunction "1_1") (pintype "passive"))
      (node (ref "SW_RST_MCU") (pin "GND1") (pinfunction "GND1_GND1") (pintype "bidirectional"))
      (node (ref "SW_RST_MCU") (pin "GND2") (pinfunction "GND2_GND2") (pintype "bidirectional"))
      (node (ref "SW_RST_MCU") (pin "P1") (pinfunction "P1_P1") (pintype "passive"))
      (node (ref "TP_GND1") (pin "P$1") (pinfunction "P$1_P$1") (pintype "bidirectional"))
      (node (ref "TP_GND2") (pin "P$1") (pinfunction "P$1_P$1") (pintype "bidirectional"))
      (node (ref "TP_GND3") (pin "P$1") (pinfunction "P$1_P$1") (pintype "bidirectional"))
      (node (ref "TP_GND4") (pin "P$1") (pinfunction "P$1_P$1") (pintype "bidirectional"))
      (node (ref "XTAL1") (pin "2") (pinfunction "GND2_2") (pintype "passive"))
      (node (ref "XTAL1") (pin "4") (pinfunction "GND4_4") (pintype "passive"))
    )
    (net (code "16") (name "I2C4_NINT") (class "Default")
      (node (ref "CON_BACKPLANE") (pin "22") (pinfunction "22_22") (pintype "bidirectional"))
      (node (ref "MCU") (pin "87") (pinfunction "PG2_87") (pintype "bidirectional"))
      (node (ref "R10") (pin "1") (pinfunction "1_1") (pintype "passive"))
    )
    (net (code "17") (name "I2C4_SCL") (class "Default")
      (node (ref "CON_BACKPLANE") (pin "24") (pinfunction "24_24") (pintype "bidirectional"))
      (node (ref "MCU") (pin "81") (pinfunction "PD12_81") (pintype "bidirectional"))
      (node (ref "R8") (pin "1") (pinfunction "1_1") (pintype "passive"))
    )
    (net (code "18") (name "I2C4_SDA") (class "Default")
      (node (ref "CON_BACKPLANE") (pin "23") (pinfunction "23_23") (pintype "bidirectional"))
      (node (ref "MCU") (pin "82") (pinfunction "PD13_82") (pintype "bidirectional"))
      (node (ref "R9") (pin "1") (pinfunction "1_1") (pintype "passive"))
    )
    (net (code "19") (name "JTCK{slash}SWCLK") (class "Default")
      (node (ref "CON_JTAG") (pin "9") (pinfunction "9_9") (pintype "passive"))
      (node (ref "MCU") (pin "109") (pinfunction "PA14_109") (pintype "bidirectional"))
    )
    (net (code "20") (name "JTDI") (class "Default")
      (node (ref "CON_JTAG") (pin "5") (pinfunction "5_5") (pintype "passive"))
      (node (ref "MCU") (pin "110") (pinfunction "PA15_110") (pintype "bidirectional"))
    )
    (net (code "21") (name "JTDO{slash}TRACESWO") (class "Default")
      (node (ref "CON_JTAG") (pin "13") (pinfunction "13_13") (pintype "passive"))
      (node (ref "MCU") (pin "133") (pinfunction "PB3_133") (pintype "bidirectional"))
    )
    (net (code "22") (name "JTMS{slash}SWDIO") (class "Default")
      (node (ref "CON_JTAG") (pin "7") (pinfunction "7_7") (pintype "passive"))
      (node (ref "MCU") (pin "105") (pinfunction "PA13_105") (pintype "bidirectional"))
    )
    (net (code "23") (name "LED1") (class "Default")
      (node (ref "IC5") (pin "2") (pinfunction "I_2") (pintype "input"))
      (node (ref "MCU") (pin "1") (pinfunction "PE2_1") (pintype "bidirectional"))
    )
    (net (code "24") (name "LED2") (class "Default")
      (node (ref "IC5") (pin "5") (pinfunction "I_5") (pintype "input"))
      (node (ref "MCU") (pin "2") (pinfunction "PE3_2") (pintype "bidirectional"))
    )
    (net (code "25") (name "LED3") (class "Default")
      (node (ref "IC5") (pin "9") (pinfunction "I_9") (pintype "input"))
      (node (ref "MCU") (pin "3") (pinfunction "PE4_3") (pintype "bidirectional"))
    )
    (net (code "26") (name "LED4") (class "Default")
      (node (ref "IC5") (pin "12") (pinfunction "I_12") (pintype "input"))
      (node (ref "MCU") (pin "4") (pinfunction "PE5_4") (pintype "bidirectional"))
    )
    (net (code "27") (name "NJTRST") (class "Default")
      (node (ref "CON_JTAG") (pin "3") (pinfunction "3_3") (pintype "passive"))
      (node (ref "MCU") (pin "134") (pinfunction "PB4_134") (pintype "bidirectional"))
    )
    (net (code "28") (name "NRST") (class "Default")
      (node (ref "C32") (pin "2") (pinfunction "2_2") (pintype "passive"))
      (node (ref "CON_JTAG") (pin "15") (pinfunction "15_15") (pintype "passive"))
      (node (ref "MCU") (pin "25") (pinfunction "NRST_25") (pintype "input"))
      (node (ref "SW_RST_MCU") (pin "P3") (pinfunction "P3_P3") (pintype "passive"))
    )
    (net (code "29") (name "Net-(CON_JTAG-Pad11)") (class "Default")
      (node (ref "CON_JTAG") (pin "11") (pinfunction "11_11") (pintype "passive"))
      (node (ref "R5") (pin "2") (pinfunction "2_2") (pintype "passive"))
    )
    (net (code "30") (name "Net-(CON_JTAG-Pad17)") (class "Default")
      (node (ref "CON_JTAG") (pin "17") (pinfunction "17_17") (pintype "passive"))
      (node (ref "R6") (pin "2") (pinfunction "2_2") (pintype "passive"))
    )
    (net (code "31") (name "Net-(CON_JTAG-Pad19)") (class "Default")
      (node (ref "CON_JTAG") (pin "19") (pinfunction "19_19") (pintype "passive"))
      (node (ref "R7") (pin "2") (pinfunction "2_2") (pintype "passive"))
    )
    (net (code "32") (name "Net-(IC2-IN)") (class "Default")
      (node (ref "C7") (pin "+") (pinfunction "+_+") (pintype "passive"))
      (node (ref "IC2") (pin "3") (pinfunction "IN_3") (pintype "input"))
      (node (ref "L1") (pin "2") (pinfunction "2_2") (pintype "passive"))
    )
    (net (code "33") (name "Net-(IC4-RBIAS)") (class "Default")
      (node (ref "IC4") (pin "32") (pinfunction "RBIAS_32") (pintype "bidirectional"))
      (node (ref "R15") (pin "2") (pinfunction "2_2") (pintype "passive"))
    )
    (net (code "34") (name "Net-(IC4-RESET)") (class "Default")
      (node (ref "IC4") (pin "9") (pinfunction "RESET_9") (pintype "input"))
      (node (ref "R19") (pin "2") (pinfunction "2_2") (pintype "passive"))
    )
    (net (code "35") (name "Net-(IC4-VBUS)") (class "Default")
      (node (ref "IC4") (pin "4") (pinfunction "VBUS_4") (pintype "bidirectional"))
      (node (ref "R18") (pin "1") (pinfunction "1_1") (pintype "passive"))
    )
    (net (code "36") (name "Net-(IC4-VDD1.8)") (class "Default")
      (node (ref "C37") (pin "1") (pinfunction "1_1") (pintype "passive"))
      (node (ref "C38") (pin "1") (pinfunction "1_1") (pintype "passive"))
      (node (ref "IC4") (pin "15") (pinfunction "VDD1.8-1_15") (pintype "power_in"))
      (node (ref "IC4") (pin "26") (pinfunction "VDD1.8_26") (pintype "power_in"))
    )
    (net (code "37") (name "Net-(IC4-VDDA1.8)") (class "Default")
      (node (ref "C39") (pin "1") (pinfunction "1_1") (pintype "passive"))
      (node (ref "C40") (pin "1") (pinfunction "1_1") (pintype "passive"))
      (node (ref "IC4") (pin "29") (pinfunction "VDDA1.8_29") (pintype "power_in"))
    )
    (net (code "38") (name "Net-(IC4-XI)") (class "Default")
      (node (ref "C42") (pin "1") (pinfunction "1_1") (pintype "passive"))
      (node (ref "IC4") (pin "28") (pinfunction "XI_28") (pintype "input"))
      (node (ref "R17") (pin "1") (pinfunction "1_1") (pintype "passive"))
      (node (ref "XTAL3") (pin "2") (pinfunction "2_2") (pintype "passive"))
    )
    (net (code "39") (name "Net-(IC4-XO)") (class "Default")
      (node (ref "C41") (pin "1") (pinfunction "1_1") (pintype "passive"))
      (node (ref "IC4") (pin "27") (pinfunction "XO_27") (pintype "output"))
      (node (ref "R17") (pin "2") (pinfunction "2_2") (pintype "passive"))
      (node (ref "XTAL3") (pin "1") (pinfunction "1_1") (pintype "passive"))
    )
    (net (code "40") (name "Net-(IC5A-O)") (class "Default")
      (node (ref "IC5") (pin "3") (pinfunction "O_3") (pintype "output"))
      (node (ref "R60") (pin "1") (pinfunction "1_1") (pintype "passive"))
    )
    (net (code "41") (name "Net-(IC5B-O)") (class "Default")
      (node (ref "IC5") (pin "6") (pinfunction "O_6") (pintype "output"))
      (node (ref "R61") (pin "1") (pinfunction "1_1") (pintype "passive"))
    )
    (net (code "42") (name "Net-(IC5C-O)") (class "Default")
      (node (ref "IC5") (pin "8") (pinfunction "O_8") (pintype "output"))
      (node (ref "R62") (pin "1") (pinfunction "1_1") (pintype "passive"))
    )
    (net (code "43") (name "Net-(IC5D-O)") (class "Default")
      (node (ref "IC5") (pin "11") (pinfunction "O_11") (pintype "output"))
      (node (ref "R63") (pin "1") (pinfunction "1_1") (pintype "passive"))
    )
    (net (code "44") (name "Net-(LED1-A)") (class "Default")
      (node (ref "LED1") (pin "+") (pinfunction "A_+") (pintype "passive"))
      (node (ref "R60") (pin "2") (pinfunction "2_2") (pintype "passive"))
    )
    (net (code "45") (name "Net-(LED2-A)") (class "Default")
      (node (ref "LED2") (pin "+") (pinfunction "A_+") (pintype "passive"))
      (node (ref "R61") (pin "2") (pinfunction "2_2") (pintype "passive"))
    )
    (net (code "46") (name "Net-(LED3-A)") (class "Default")
      (node (ref "LED3") (pin "+") (pinfunction "A_+") (pintype "passive"))
      (node (ref "R62") (pin "2") (pinfunction "2_2") (pintype "passive"))
    )
    (net (code "47") (name "Net-(LED4-A)") (class "Default")
      (node (ref "LED4") (pin "+") (pinfunction "A_+") (pintype "passive"))
      (node (ref "R63") (pin "2") (pinfunction "2_2") (pintype "passive"))
    )
    (net (code "48") (name "Net-(LED_+3.3V_VDD-PadC)") (class "Default")
      (node (ref "LED_+3.3V_VDD") (pin "C") (pinfunction "C_C") (pintype "passive"))
      (node (ref "R1") (pin "1") (pinfunction "1_1") (pintype "passive"))
    )
    (net (code "49") (name "Net-(LED_+3V3_VDDA-PadC)") (class "Default")
      (node (ref "LED_+3V3_VDDA") (pin "C") (pinfunction "C_C") (pintype "passive"))
      (node (ref "R2") (pin "1") (pinfunction "1_1") (pintype "passive"))
    )
    (net (code "50") (name "Net-(LED_DEBUG1-PadC)") (class "Default")
      (node (ref "LED_DEBUG1") (pin "C") (pinfunction "C_C") (pintype "passive"))
      (node (ref "R64") (pin "1") (pinfunction "1_1") (pintype "passive"))
    )
    (net (code "51") (name "Net-(LED_DEBUG2-PadC)") (class "Default")
      (node (ref "LED_DEBUG2") (pin "C") (pinfunction "C_C") (pintype "passive"))
      (node (ref "R65") (pin "1") (pinfunction "1_1") (pintype "passive"))
    )
    (net (code "52") (name "Net-(LED_DEBUG3-PadC)") (class "Default")
      (node (ref "LED_DEBUG3") (pin "C") (pinfunction "C_C") (pintype "passive"))
      (node (ref "R66") (pin "1") (pinfunction "1_1") (pintype "passive"))
    )
    (net (code "53") (name "Net-(LED_DEBUG4-PadC)") (class "Default")
      (node (ref "LED_DEBUG4") (pin "C") (pinfunction "C_C") (pintype "passive"))
      (node (ref "R67") (pin "1") (pinfunction "1_1") (pintype "passive"))
    )
    (net (code "54") (name "Net-(MCU-BOOT0)") (class "Default")
      (node (ref "MCU") (pin "138") (pinfunction "BOOT0_138") (pintype "input"))
      (node (ref "R4") (pin "2") (pinfunction "2_2") (pintype "passive"))
    )
    (net (code "55") (name "Net-(MCU-PC14-OSC32_IN)") (class "Default")
      (node (ref "C45") (pin "1") (pinfunction "1_1") (pintype "passive"))
      (node (ref "MCU") (pin "8") (pinfunction "PC14-OSC32_IN_8") (pintype "bidirectional"))
      (node (ref "XTAL2") (pin "1") (pinfunction "1_1") (pintype "passive"))
    )
    (net (code "56") (name "Net-(MCU-PC15-OSC32_OUT)") (class "Default")
      (node (ref "C46") (pin "1") (pinfunction "1_1") (pintype "passive"))
      (node (ref "MCU") (pin "9") (pinfunction "PC15-OSC32_OUT_9") (pintype "bidirectional"))
      (node (ref "XTAL2") (pin "2") (pinfunction "2_2") (pintype "passive"))
    )
    (net (code "57") (name "Net-(MCU-PDR_ON)") (class "Default")
      (node (ref "MCU") (pin "143") (pinfunction "PDR_ON_143") (pintype "input"))
      (node (ref "R3") (pin "1") (pinfunction "1_1") (pintype "passive"))
    )
    (net (code "58") (name "Net-(MCU-PH0-OSC_IN)") (class "Default")
      (node (ref "C44") (pin "1") (pinfunction "1_1") (pintype "passive"))
      (node (ref "MCU") (pin "23") (pinfunction "PH0-OSC_IN_23") (pintype "bidirectional"))
      (node (ref "XTAL1") (pin "3") (pinfunction "3_3") (pintype "passive"))
    )
    (net (code "59") (name "Net-(MCU-PH1-OSC_OUT)") (class "Default")
      (node (ref "C43") (pin "1") (pinfunction "1_1") (pintype "passive"))
      (node (ref "MCU") (pin "24") (pinfunction "PH1-OSC_OUT_24") (pintype "bidirectional"))
      (node (ref "XTAL1") (pin "1") (pinfunction "1_1") (pintype "passive"))
    )
    (net (code "60") (name "Net-(R4-Pad1)") (class "Default")
      (node (ref "R4") (pin "1") (pinfunction "1_1") (pintype "passive"))
      (node (ref "SJ1") (pin "2") (pinfunction "2_2") (pintype "passive"))
    )
    (net (code "61") (name "Net-(R15-Pad1)") (class "Default")
      (node (ref "R15") (pin "1") (pinfunction "1_1") (pintype "passive"))
      (node (ref "R16") (pin "2") (pinfunction "2_2") (pintype "passive"))
    )
    (net (code "62") (name "SPI2_MOSI") (class "Default")
      (node (ref "CON_BACKPLANE") (pin "18") (pinfunction "18_18") (pintype "bidirectional"))
      (node (ref "MCU") (pin "76") (pinfunction "PB15_76") (pintype "bidirectional"))
    )
    (net (code "63") (name "SPI2_NSS") (class "Default")
      (node (ref "CON_BACKPLANE") (pin "16") (pinfunction "16_16") (pintype "bidirectional"))
      (node (ref "MCU") (pin "140") (pinfunction "PB9_140") (pintype "bidirectional"))
    )
    (net (code "64") (name "SPI2_SCK") (class "Default")
      (node (ref "CON_BACKPLANE") (pin "17") (pinfunction "17_17") (pintype "bidirectional"))
      (node (ref "MCU") (pin "117") (pinfunction "PD3_117") (pintype "bidirectional"))
    )
    (net (code "65") (name "SPI3_MISO") (class "Default")
      (node (ref "CON_BACKPLANE") (pin "19") (pinfunction "19_19") (pintype "bidirectional"))
      (node (ref "MCU") (pin "112") (pinfunction "PC11_112") (pintype "bidirectional"))
    )
    (net (code "66") (name "SPI3_MOSI") (class "Default")
      (node (ref "CON_BACKPLANE") (pin "20") (pinfunction "20_20") (pintype "bidirectional"))
      (node (ref "MCU") (pin "122") (pinfunction "PD6_122") (pintype "bidirectional"))
    )
    (net (code "67") (name "SPI3_SCK") (class "Default")
      (node (ref "CON_BACKPLANE") (pin "21") (pinfunction "21_21") (pintype "bidirectional"))
      (node (ref "MCU") (pin "111") (pinfunction "PC10_111") (pintype "bidirectional"))
    )
    (net (code "68") (name "ULPI_CLK") (class "Default")
      (node (ref "IC4") (pin "14") (pinfunction "CLKOUT_14") (pintype "output"))
      (node (ref "MCU") (pin "41") (pinfunction "PA5_41") (pintype "bidirectional"))
    )
    (net (code "69") (name "ULPI_DATA0") (class "Default")
      (node (ref "IC4") (pin "24") (pinfunction "DATA[0]_24") (pintype "bidirectional"))
      (node (ref "MCU") (pin "37") (pinfunction "PA3_37") (pintype "bidirectional"))
    )
    (net (code "70") (name "ULPI_DATA1") (class "Default")
      (node (ref "IC4") (pin "23") (pinfunction "DATA[1]_23") (pintype "bidirectional"))
      (node (ref "MCU") (pin "46") (pinfunction "PB0_46") (pintype "bidirectional"))
    )
    (net (code "71") (name "ULPI_DATA2") (class "Default")
      (node (ref "IC4") (pin "22") (pinfunction "DATA[2]_22") (pintype "bidirectional"))
      (node (ref "MCU") (pin "47") (pinfunction "PB1_47") (pintype "bidirectional"))
    )
    (net (code "72") (name "ULPI_DATA3") (class "Default")
      (node (ref "IC4") (pin "21") (pinfunction "DATA[3]_21") (pintype "bidirectional"))
      (node (ref "MCU") (pin "69") (pinfunction "PB10_69") (pintype "bidirectional"))
    )
    (net (code "73") (name "ULPI_DATA4") (class "Default")
      (node (ref "IC4") (pin "20") (pinfunction "DATA[4]_20") (pintype "bidirectional"))
      (node (ref "MCU") (pin "70") (pinfunction "PB11_70") (pintype "bidirectional"))
    )
    (net (code "74") (name "ULPI_DATA5") (class "Default")
      (node (ref "IC4") (pin "19") (pinfunction "DATA[5]_19") (pintype "bidirectional"))
      (node (ref "MCU") (pin "73") (pinfunction "PB12_73") (pintype "bidirectional"))
    )
    (net (code "75") (name "ULPI_DATA6") (class "Default")
      (node (ref "IC4") (pin "18") (pinfunction "DATA[6]_18") (pintype "bidirectional"))
      (node (ref "MCU") (pin "74") (pinfunction "PB13_74") (pintype "bidirectional"))
    )
    (net (code "76") (name "ULPI_DATA7") (class "Default")
      (node (ref "IC4") (pin "17") (pinfunction "DATA[7]_17") (pintype "bidirectional"))
      (node (ref "MCU") (pin "135") (pinfunction "PB5_135") (pintype "bidirectional"))
    )
    (net (code "77") (name "ULPI_DIR") (class "Default")
      (node (ref "IC4") (pin "12") (pinfunction "DIR_12") (pintype "output"))
      (node (ref "MCU") (pin "28") (pinfunction "PC2_C_28") (pintype "bidirectional"))
    )
    (net (code "78") (name "ULPI_NXT") (class "Default")
      (node (ref "IC4") (pin "11") (pinfunction "NXT_11") (pintype "output"))
      (node (ref "MCU") (pin "29") (pinfunction "PC3_C_29") (pintype "bidirectional"))
    )
    (net (code "79") (name "ULPI_STP") (class "Default")
      (node (ref "IC4") (pin "13") (pinfunction "STP_13") (pintype "input"))
      (node (ref "MCU") (pin "26") (pinfunction "PC0_26") (pintype "bidirectional"))
    )
    (net (code "80") (name "USART1_RX") (class "Default")
      (node (ref "CON_BACKPLANE") (pin "25") (pinfunction "25_25") (pintype "bidirectional"))
      (node (ref "MCU") (pin "137") (pinfunction "PB7_137") (pintype "bidirectional"))
    )
    (net (code "81") (name "USART1_TX") (class "Default")
      (node (ref "CON_BACKPLANE") (pin "26") (pinfunction "26_26") (pintype "bidirectional"))
      (node (ref "MCU") (pin "136") (pinfunction "PB6_136") (pintype "bidirectional"))
    )
    (net (code "82") (name "USB_DATA_DM") (class "Default")
      (node (ref "CON_BACKPLANE") (pin "30") (pinfunction "30_30") (pintype "bidirectional"))
      (node (ref "IC4") (pin "8") (pinfunction "DM_8") (pintype "bidirectional"))
    )
    (net (code "83") (name "USB_DATA_DP") (class "Default")
      (node (ref "CON_BACKPLANE") (pin "29") (pinfunction "29_29") (pintype "bidirectional"))
      (node (ref "IC4") (pin "7") (pinfunction "DP_7") (pintype "bidirectional"))
    )
    (net (code "84") (name "VBUS_USB_DATA") (class "Default")
      (node (ref "CON_BACKPLANE") (pin "28") (pinfunction "28_28") (pintype "bidirectional"))
      (node (ref "R18") (pin "2") (pinfunction "2_2") (pintype "passive"))
    )
    (net (code "85") (name "VCAP") (class "Default")
      (node (ref "C30") (pin "1") (pinfunction "1_1") (pintype "passive"))
      (node (ref "C31") (pin "1") (pinfunction "1_1") (pintype "passive"))
      (node (ref "MCU") (pin "106") (pinfunction "VCAP_106") (pintype "power_in"))
      (node (ref "MCU") (pin "71") (pinfunction "VCAP_71") (pintype "power_in"))
    )
    (net (code "86") (name "unconnected-(IC4-CPEN-Pad3)") (class "Default")
      (node (ref "IC4") (pin "3") (pinfunction "CPEN_3") (pintype "output"))
    )
    (net (code "87") (name "unconnected-(IC4-EXTVBUS-Pad10)") (class "Default")
      (node (ref "IC4") (pin "10") (pinfunction "EXTVBUS_10") (pintype "input"))
    )
    (net (code "88") (name "unconnected-(IC4-ID-Pad5)") (class "Default")
      (node (ref "IC4") (pin "5") (pinfunction "ID_5") (pintype "input"))
    )
    (net (code "89") (name "unconnected-(MCU-PA0-Pad34)") (class "Default")
      (node (ref "MCU") (pin "34") (pinfunction "PA0_34") (pintype "bidirectional"))
    )
    (net (code "90") (name "unconnected-(MCU-PA1-Pad35)") (class "Default")
      (node (ref "MCU") (pin "35") (pinfunction "PA1_35") (pintype "bidirectional"))
    )
    (net (code "91") (name "unconnected-(MCU-PA2-Pad36)") (class "Default")
      (node (ref "MCU") (pin "36") (pinfunction "PA2_36") (pintype "bidirectional"))
    )
    (net (code "92") (name "unconnected-(MCU-PA4-Pad40)") (class "Default")
      (node (ref "MCU") (pin "40") (pinfunction "PA4_40") (pintype "bidirectional"))
    )
    (net (code "93") (name "unconnected-(MCU-PA6-Pad42)") (class "Default")
      (node (ref "MCU") (pin "42") (pinfunction "PA6_42") (pintype "bidirectional"))
    )
    (net (code "94") (name "unconnected-(MCU-PA7-Pad43)") (class "Default")
      (node (ref "MCU") (pin "43") (pinfunction "PA7_43") (pintype "bidirectional"))
    )
    (net (code "95") (name "unconnected-(MCU-PA8-Pad100)") (class "Default")
      (node (ref "MCU") (pin "100") (pinfunction "PA8_100") (pintype "bidirectional"))
    )
    (net (code "96") (name "unconnected-(MCU-PA9-Pad101)") (class "Default")
      (node (ref "MCU") (pin "101") (pinfunction "PA9_101") (pintype "bidirectional"))
    )
    (net (code "97") (name "unconnected-(MCU-PA10-Pad102)") (class "Default")
      (node (ref "MCU") (pin "102") (pinfunction "PA10_102") (pintype "bidirectional"))
    )
    (net (code "98") (name "unconnected-(MCU-PA11-Pad103)") (class "Default")
      (node (ref "MCU") (pin "103") (pinfunction "PA11_103") (pintype "bidirectional"))
    )
    (net (code "99") (name "unconnected-(MCU-PA12-Pad104)") (class "Default")
      (node (ref "MCU") (pin "104") (pinfunction "PA12_104") (pintype "bidirectional"))
    )
    (net (code "100") (name "unconnected-(MCU-PB2-Pad48)") (class "Default")
      (node (ref "MCU") (pin "48") (pinfunction "PB2_48") (pintype "bidirectional"))
    )
    (net (code "101") (name "unconnected-(MCU-PB8-Pad139)") (class "Default")
      (node (ref "MCU") (pin "139") (pinfunction "PB8_139") (pintype "bidirectional"))
    )
    (net (code "102") (name "unconnected-(MCU-PB14-Pad75)") (class "Default")
      (node (ref "MCU") (pin "75") (pinfunction "PB14_75") (pintype "bidirectional"))
    )
    (net (code "103") (name "unconnected-(MCU-PC1-Pad27)") (class "Default")
      (node (ref "MCU") (pin "27") (pinfunction "PC1_27") (pintype "bidirectional"))
    )
    (net (code "104") (name "unconnected-(MCU-PC4-Pad44)") (class "Default")
      (node (ref "MCU") (pin "44") (pinfunction "PC4_44") (pintype "bidirectional"))
    )
    (net (code "105") (name "unconnected-(MCU-PC5-Pad45)") (class "Default")
      (node (ref "MCU") (pin "45") (pinfunction "PC5_45") (pintype "bidirectional"))
    )
    (net (code "106") (name "unconnected-(MCU-PC6-Pad96)") (class "Default")
      (node (ref "MCU") (pin "96") (pinfunction "PC6_96") (pintype "bidirectional"))
    )
    (net (code "107") (name "unconnected-(MCU-PC7-Pad97)") (class "Default")
      (node (ref "MCU") (pin "97") (pinfunction "PC7_97") (pintype "bidirectional"))
    )
    (net (code "108") (name "unconnected-(MCU-PC8-Pad98)") (class "Default")
      (node (ref "MCU") (pin "98") (pinfunction "PC8_98") (pintype "bidirectional"))
    )
    (net (code "109") (name "unconnected-(MCU-PC9-Pad99)") (class "Default")
      (node (ref "MCU") (pin "99") (pinfunction "PC9_99") (pintype "bidirectional"))
    )
    (net (code "110") (name "unconnected-(MCU-PC12-Pad113)") (class "Default")
      (node (ref "MCU") (pin "113") (pinfunction "PC12_113") (pintype "bidirectional"))
    )
    (net (code "111") (name "unconnected-(MCU-PC13-Pad7)") (class "Default")
      (node (ref "MCU") (pin "7") (pinfunction "PC13_7") (pintype "bidirectional"))
    )
    (net (code "112") (name "unconnected-(MCU-PD0-Pad114)") (class "Default")
      (node (ref "MCU") (pin "114") (pinfunction "PD0_114") (pintype "bidirectional"))
    )
    (net (code "113") (name "unconnected-(MCU-PD1-Pad115)") (class "Default")
      (node (ref "MCU") (pin "115") (pinfunction "PD1_115") (pintype "bidirectional"))
    )
    (net (code "114") (name "unconnected-(MCU-PD2-Pad116)") (class "Default")
      (node (ref "MCU") (pin "116") (pinfunction "PD2_116") (pintype "bidirectional"))
    )
    (net (code "115") (name "unconnected-(MCU-PD4-Pad118)") (class "Default")
      (node (ref "MCU") (pin "118") (pinfunction "PD4_118") (pintype "bidirectional"))
    )
    (net (code "116") (name "unconnected-(MCU-PD5-Pad119)") (class "Default")
      (node (ref "MCU") (pin "119") (pinfunction "PD5_119") (pintype "bidirectional"))
    )
    (net (code "117") (name "unconnected-(MCU-PD7-Pad123)") (class "Default")
      (node (ref "MCU") (pin "123") (pinfunction "PD7_123") (pintype "bidirectional"))
    )
    (net (code "118") (name "unconnected-(MCU-PD8-Pad77)") (class "Default")
      (node (ref "MCU") (pin "77") (pinfunction "PD8_77") (pintype "bidirectional"))
    )
    (net (code "119") (name "unconnected-(MCU-PD9-Pad78)") (class "Default")
      (node (ref "MCU") (pin "78") (pinfunction "PD9_78") (pintype "bidirectional"))
    )
    (net (code "120") (name "unconnected-(MCU-PD10-Pad79)") (class "Default")
      (node (ref "MCU") (pin "79") (pinfunction "PD10_79") (pintype "bidirectional"))
    )
    (net (code "121") (name "unconnected-(MCU-PD11-Pad80)") (class "Default")
      (node (ref "MCU") (pin "80") (pinfunction "PD11_80") (pintype "bidirectional"))
    )
    (net (code "122") (name "unconnected-(MCU-PD14-Pad85)") (class "Default")
      (node (ref "MCU") (pin "85") (pinfunction "PD14_85") (pintype "bidirectional"))
    )
    (net (code "123") (name "unconnected-(MCU-PD15-Pad86)") (class "Default")
      (node (ref "MCU") (pin "86") (pinfunction "PD15_86") (pintype "bidirectional"))
    )
    (net (code "124") (name "unconnected-(MCU-PE0-Pad141)") (class "Default")
      (node (ref "MCU") (pin "141") (pinfunction "PE0_141") (pintype "bidirectional"))
    )
    (net (code "125") (name "unconnected-(MCU-PE1-Pad142)") (class "Default")
      (node (ref "MCU") (pin "142") (pinfunction "PE1_142") (pintype "bidirectional"))
    )
    (net (code "126") (name "unconnected-(MCU-PE6-Pad5)") (class "Default")
      (node (ref "MCU") (pin "5") (pinfunction "PE6_5") (pintype "bidirectional"))
    )
    (net (code "127") (name "unconnected-(MCU-PE7-Pad58)") (class "Default")
      (node (ref "MCU") (pin "58") (pinfunction "PE7_58") (pintype "bidirectional"))
    )
    (net (code "128") (name "unconnected-(MCU-PE8-Pad59)") (class "Default")
      (node (ref "MCU") (pin "59") (pinfunction "PE8_59") (pintype "bidirectional"))
    )
    (net (code "129") (name "unconnected-(MCU-PE9-Pad60)") (class "Default")
      (node (ref "MCU") (pin "60") (pinfunction "PE9_60") (pintype "bidirectional"))
    )
    (net (code "130") (name "unconnected-(MCU-PE14-Pad67)") (class "Default")
      (node (ref "MCU") (pin "67") (pinfunction "PE14_67") (pintype "bidirectional"))
    )
    (net (code "131") (name "unconnected-(MCU-PE15-Pad68)") (class "Default")
      (node (ref "MCU") (pin "68") (pinfunction "PE15_68") (pintype "bidirectional"))
    )
    (net (code "132") (name "unconnected-(MCU-PF0-Pad10)") (class "Default")
      (node (ref "MCU") (pin "10") (pinfunction "PF0_10") (pintype "bidirectional"))
    )
    (net (code "133") (name "unconnected-(MCU-PF1-Pad11)") (class "Default")
      (node (ref "MCU") (pin "11") (pinfunction "PF1_11") (pintype "bidirectional"))
    )
    (net (code "134") (name "unconnected-(MCU-PF2-Pad12)") (class "Default")
      (node (ref "MCU") (pin "12") (pinfunction "PF2_12") (pintype "bidirectional"))
    )
    (net (code "135") (name "unconnected-(MCU-PF3-Pad13)") (class "Default")
      (node (ref "MCU") (pin "13") (pinfunction "PF3_13") (pintype "bidirectional"))
    )
    (net (code "136") (name "unconnected-(MCU-PF4-Pad14)") (class "Default")
      (node (ref "MCU") (pin "14") (pinfunction "PF4_14") (pintype "bidirectional"))
    )
    (net (code "137") (name "unconnected-(MCU-PF5-Pad15)") (class "Default")
      (node (ref "MCU") (pin "15") (pinfunction "PF5_15") (pintype "bidirectional"))
    )
    (net (code "138") (name "unconnected-(MCU-PF6-Pad18)") (class "Default")
      (node (ref "MCU") (pin "18") (pinfunction "PF6_18") (pintype "bidirectional"))
    )
    (net (code "139") (name "unconnected-(MCU-PF7-Pad19)") (class "Default")
      (node (ref "MCU") (pin "19") (pinfunction "PF7_19") (pintype "bidirectional"))
    )
    (net (code "140") (name "unconnected-(MCU-PF8-Pad20)") (class "Default")
      (node (ref "MCU") (pin "20") (pinfunction "PF8_20") (pintype "bidirectional"))
    )
    (net (code "141") (name "unconnected-(MCU-PF9-Pad21)") (class "Default")
      (node (ref "MCU") (pin "21") (pinfunction "PF9_21") (pintype "bidirectional"))
    )
    (net (code "142") (name "unconnected-(MCU-PF10-Pad22)") (class "Default")
      (node (ref "MCU") (pin "22") (pinfunction "PF10_22") (pintype "bidirectional"))
    )
    (net (code "143") (name "unconnected-(MCU-PF11-Pad49)") (class "Default")
      (node (ref "MCU") (pin "49") (pinfunction "PF11_49") (pintype "bidirectional"))
    )
    (net (code "144") (name "unconnected-(MCU-PF12-Pad50)") (class "Default")
      (node (ref "MCU") (pin "50") (pinfunction "PF12_50") (pintype "bidirectional"))
    )
    (net (code "145") (name "unconnected-(MCU-PF13-Pad53)") (class "Default")
      (node (ref "MCU") (pin "53") (pinfunction "PF13_53") (pintype "bidirectional"))
    )
    (net (code "146") (name "unconnected-(MCU-PF14-Pad54)") (class "Default")
      (node (ref "MCU") (pin "54") (pinfunction "PF14_54") (pintype "bidirectional"))
    )
    (net (code "147") (name "unconnected-(MCU-PF15-Pad55)") (class "Default")
      (node (ref "MCU") (pin "55") (pinfunction "PF15_55") (pintype "bidirectional"))
    )
    (net (code "148") (name "unconnected-(MCU-PG0-Pad56)") (class "Default")
      (node (ref "MCU") (pin "56") (pinfunction "PG0_56") (pintype "bidirectional"))
    )
    (net (code "149") (name "unconnected-(MCU-PG1-Pad57)") (class "Default")
      (node (ref "MCU") (pin "57") (pinfunction "PG1_57") (pintype "bidirectional"))
    )
    (net (code "150") (name "unconnected-(MCU-PG3-Pad88)") (class "Default")
      (node (ref "MCU") (pin "88") (pinfunction "PG3_88") (pintype "bidirectional"))
    )
    (net (code "151") (name "unconnected-(MCU-PG4-Pad89)") (class "Default")
      (node (ref "MCU") (pin "89") (pinfunction "PG4_89") (pintype "bidirectional"))
    )
    (net (code "152") (name "unconnected-(MCU-PG5-Pad90)") (class "Default")
      (node (ref "MCU") (pin "90") (pinfunction "PG5_90") (pintype "bidirectional"))
    )
    (net (code "153") (name "unconnected-(MCU-PG6-Pad91)") (class "Default")
      (node (ref "MCU") (pin "91") (pinfunction "PG6_91") (pintype "bidirectional"))
    )
    (net (code "154") (name "unconnected-(MCU-PG7-Pad92)") (class "Default")
      (node (ref "MCU") (pin "92") (pinfunction "PG7_92") (pintype "bidirectional"))
    )
    (net (code "155") (name "unconnected-(MCU-PG8-Pad93)") (class "Default")
      (node (ref "MCU") (pin "93") (pinfunction "PG8_93") (pintype "bidirectional"))
    )
    (net (code "156") (name "unconnected-(MCU-PG9-Pad124)") (class "Default")
      (node (ref "MCU") (pin "124") (pinfunction "PG9_124") (pintype "bidirectional"))
    )
    (net (code "157") (name "unconnected-(MCU-PG10-Pad125)") (class "Default")
      (node (ref "MCU") (pin "125") (pinfunction "PG10_125") (pintype "bidirectional"))
    )
    (net (code "158") (name "unconnected-(MCU-PG11-Pad126)") (class "Default")
      (node (ref "MCU") (pin "126") (pinfunction "PG11_126") (pintype "bidirectional"))
    )
    (net (code "159") (name "unconnected-(MCU-PG12-Pad127)") (class "Default")
      (node (ref "MCU") (pin "127") (pinfunction "PG12_127") (pintype "bidirectional"))
    )
    (net (code "160") (name "unconnected-(MCU-PG13-Pad128)") (class "Default")
      (node (ref "MCU") (pin "128") (pinfunction "PG13_128") (pintype "bidirectional"))
    )
    (net (code "161") (name "unconnected-(MCU-PG14-Pad129)") (class "Default")
      (node (ref "MCU") (pin "129") (pinfunction "PG14_129") (pintype "bidirectional"))
    )
    (net (code "162") (name "unconnected-(MCU-PG15-Pad132)") (class "Default")
      (node (ref "MCU") (pin "132") (pinfunction "PG15_132") (pintype "bidirectional"))
    )
  )
)
